# CODEC_2_OUTPUT_BUFFER.net
KiCad netlist of a schematic drawn in Altium Designer
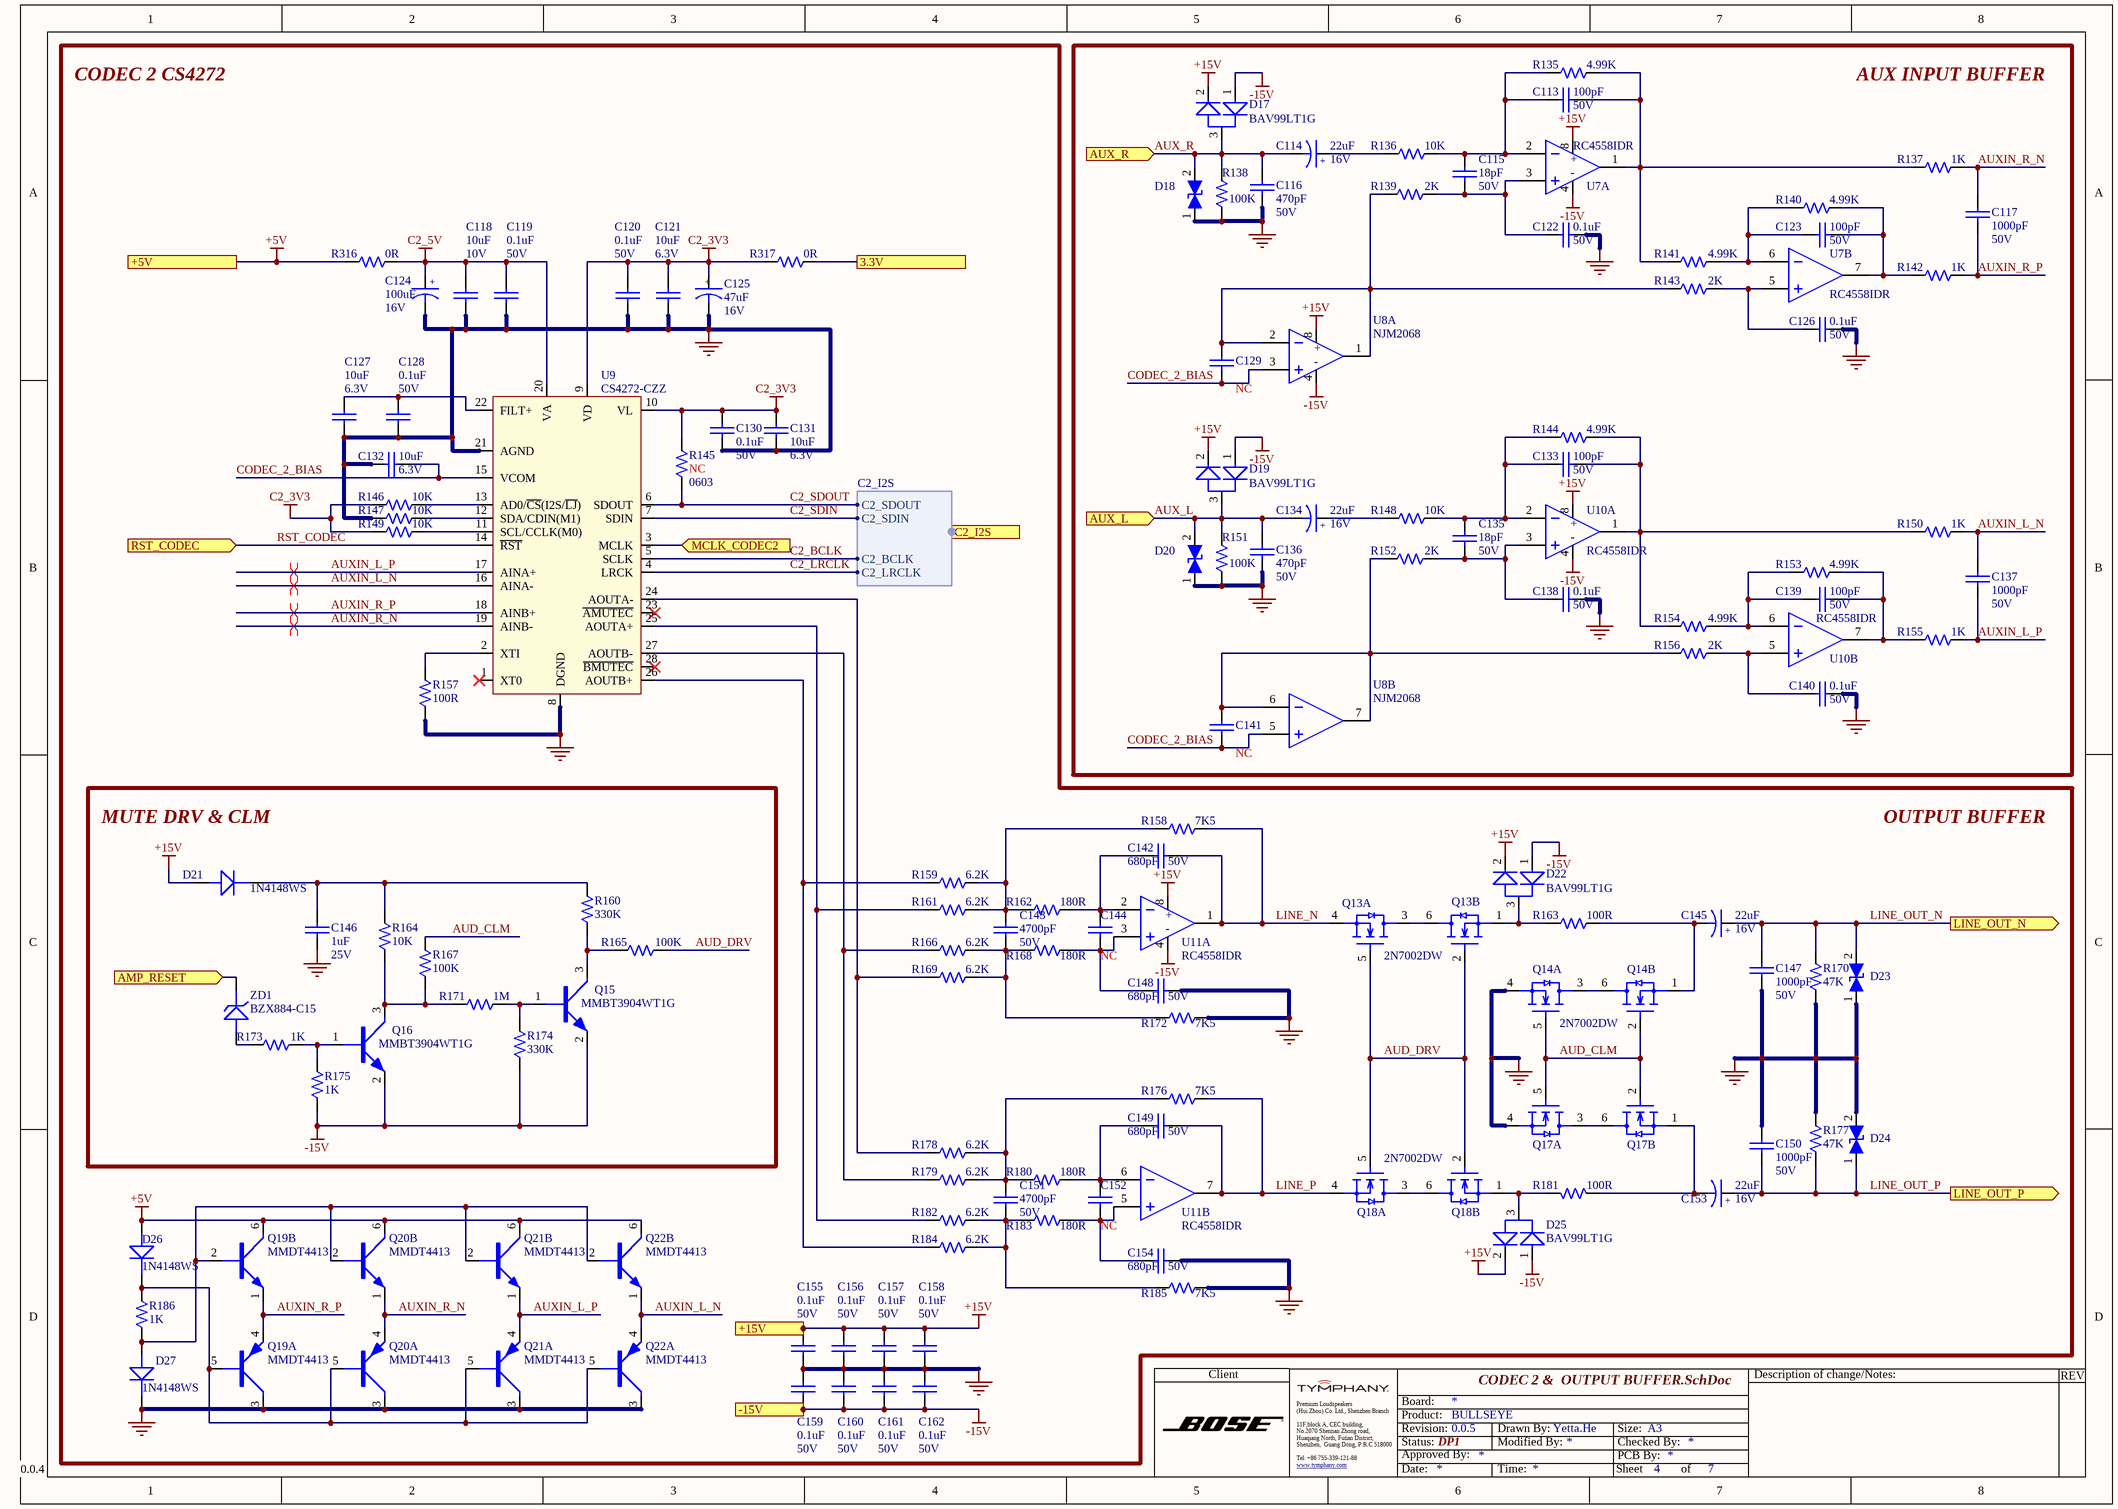
[diagram p0: CODEC 2 &  OUTPUT BUFFER.SchDoc]

(export (version "E")
  (design (tool "Eeschema 10.0.6"))
  (components
    (comp (ref "C113")
      (value "100pF")
      (footprint "CAPC0603-RW")
      (description "CAP NPO 100PF 50V +-2% 0603 WALSIN L")
      (fields
        (field (name "MFG") "WALSIN")
        (field (name "TOLERANCE") "2%")
        (field (name "VOLTAGE") "50V")
        (field (name "CREATE_NAME") "Nathan")
      )
      (libsource (lib "P-Capacitors") (part "CAP0603 100pF 50V 2%_NPO_WALSIN"))
    )
    (comp (ref "C114")
      (value "22uF")
      (footprint "CASE - B")
      (description "E 22UF 16V +-20% 4.3X4. VEJ220M1C K")
      (fields
        (field (name "MFG") "LELON")
        (field (name "MFG PART") "VEJ220M1CTR-0405")
        (field (name "VOLTAGE") "16V")
        (field (name "CREATE_NAME") "Nathan")
      )
      (libsource (lib "P-Capacitors") (part "CAP E 22uF 16V 20% SMD_VEJ220M1CTR-0405"))
    )
    (comp (ref "C115")
      (value "18pF")
      (footprint "P-Capacitors:CAPC0603-RW")
      (description "CHIP CAP 18pF 50V 5% 0603 TYPE NPO")
      (fields
        (field (name "TOLERANCE") "5%")
        (field (name "VOLTAGE") "50V")
        (field (name "Comment") "PXL410370-1800")
      )
      (libsource (lib "P-Capacitors") (part "CAP0603 18pF 50V 5% - PXL410370-1800"))
    )
    (comp (ref "C116")
      (value "470pF")
      (footprint "CAPC0603-RW")
      (description "CAP NPO 470PF 50V +-2% 0603 WALSIN L")
      (fields
        (field (name "MFG") "WALSIN")
        (field (name "TOLERANCE") "2%")
        (field (name "VOLTAGE") "50V")
        (field (name "CREATE_NAME") "Nathan")
      )
      (libsource (lib "P-Capacitors") (part "CAP0603 470pF 50V 2%_NPO_WALSIN"))
    )
    (comp (ref "C117")
      (value "1000pF")
      (footprint "CAPC0603-RW")
      (description "CAP NPO 1000P 50V +-2% 0603 WALSIN L")
      (fields
        (field (name "MFG") "WALSIN")
        (field (name "TOLERANCE") "2%")
        (field (name "VOLTAGE") "50V")
        (field (name "CREATE_NAME") "Nathan")
      )
      (libsource (lib "P-Capacitors") (part "CAP0603 1000pF 50V 2%_NPO_WALSIN"))
    )
    (comp (ref "C118")
      (value "10uF")
      (footprint "CAPC0603-RW")
      (description "CAP 10UF 10V +-20% 0603X5R SAMSUNG L")
      (fields
        (field (name "MFG") "SAMSUNG")
        (field (name "TOLERANCE") "20%,")
        (field (name "VOLTAGE") "10V")
        (field (name "CREATE_NAME") "Nathan")
      )
      (libsource (lib "P-Capacitors") (part "CAP0603 10uF 10V 20%_X5R_SAMSUNG"))
    )
    (comp (ref "C119")
      (value "0.1uF")
      (footprint "CAPC0402-RW")
      (description "CAP X7R .10UF 50V +-10% 0402 WALSIN L")
      (fields
        (field (name "TOLERANCE") "10%")
        (field (name "VOLTAGE") "50V")
        (field (name "Comment") "PWL456470-1040")
        (field (name "CREATE_NAME") "TOM@Deftronics")
      )
      (libsource (lib "P-Capacitors") (part "CAP0402 0.1uF 50V 10%"))
    )
    (comp (ref "C120")
      (value "0.1uF")
      (footprint "CAPC0402-RW")
      (description "CAP X7R .10UF 50V +-10% 0402 WALSIN L")
      (fields
        (field (name "TOLERANCE") "10%")
        (field (name "VOLTAGE") "50V")
        (field (name "Comment") "PWL456470-1040")
        (field (name "CREATE_NAME") "TOM@Deftronics")
      )
      (libsource (lib "P-Capacitors") (part "CAP0402 0.1uF 50V 10%"))
    )
    (comp (ref "C121")
      (value "10uF")
      (footprint "CAPC0603-RW")
      (description "CAP X5R 10UF 6.3V +-10% 0603 SAMSUN L")
      (fields
        (field (name "MFG") "SAMSUNG")
        (field (name "MFG PART") "CL10A106KQ8NNNC")
        (field (name "VOLTAGE") "6.3V")
        (field (name "CREATE_NAME") "Nathan")
      )
      (libsource (lib "P-Capacitors") (part "CAP0603 10uF 6.3V 10%_X5R_SAMSUNG"))
    )
    (comp (ref "C122")
      (value "0.1uF")
      (footprint "CAPC0603-RW")
      (description "GP CHIP CAP 0.1uF 50V 10% 0603 TYPE X7R")
      (fields
        (field (name "TOLERANCE") "10%")
        (field (name "VOLTAGE") "50V")
        (field (name "Comment") "PXL456470-1040")
      )
      (libsource (lib "P-Capacitors") (part "CAP0603 0.1uF 50V 10% - PXL456470-1040"))
    )
    (comp (ref "C123")
      (value "100pF")
      (footprint "CAPC0603-RW")
      (description "CAP NPO 100PF 50V +-2% 0603 WALSIN L")
      (fields
        (field (name "MFG") "WALSIN")
        (field (name "TOLERANCE") "2%")
        (field (name "VOLTAGE") "50V")
        (field (name "CREATE_NAME") "Nathan")
      )
      (libsource (lib "P-Capacitors") (part "CAP0603 100pF 50V 2%_NPO_WALSIN"))
    )
    (comp (ref "C124")
      (value "100uF")
      (footprint "CASE - D")
      (description "E 100UF 16V +-20% 6.3*5. VZH101M1C L")
      (fields
        (field (name "MFG") "LELON")
        (field (name "MFG PART") "VZH101M1CTR-0605")
        (field (name "VOLTAGE") "16V")
        (field (name "CREATE_NAME") "Nathan")
      )
      (libsource (lib "P-Capacitors") (part "CAP E 100uF 16V 20% SMD-VZH101M1CTR-0605"))
    )
    (comp (ref "C125")
      (value "47uF")
      (footprint "CASE - C5.7")
      (description "E 47UF 16V +-20% 5X6 VEJ470M1C K")
      (fields
        (field (name "MFG") "LELON")
        (field (name "MFG PART") "VEJ470M1CTR-0506")
        (field (name "VOLTAGE") "16V")
        (field (name "CREATE_NAME") "Nathan")
      )
      (libsource (lib "P-Capacitors") (part "CAP E 47uF 16V 20% SMD_VEJ470M1CTR-0506"))
    )
    (comp (ref "C126")
      (value "0.1uF")
      (footprint "CAPC0603-RW")
      (description "GP CHIP CAP 0.1uF 50V 10% 0603 TYPE X7R")
      (fields
        (field (name "TOLERANCE") "10%")
        (field (name "VOLTAGE") "50V")
        (field (name "Comment") "PXL456470-1040")
      )
      (libsource (lib "P-Capacitors") (part "CAP0603 0.1uF 50V 10% - PXL456470-1040"))
    )
    (comp (ref "C127")
      (value "10uF")
      (footprint "CAPC0603-RW")
      (description "CAP X5R 10UF 6.3V +-10% 0603 SAMSUN L")
      (fields
        (field (name "MFG") "SAMSUNG")
        (field (name "MFG PART") "CL10A106KQ8NNNC")
        (field (name "VOLTAGE") "6.3V")
        (field (name "CREATE_NAME") "Nathan")
      )
      (libsource (lib "P-Capacitors") (part "CAP0603 10uF 6.3V 10%_X5R_SAMSUNG"))
    )
    (comp (ref "C128")
      (value "0.1uF")
      (footprint "CAPC0402-RW")
      (description "CAP X7R .10UF 50V +-10% 0402 WALSIN L")
      (fields
        (field (name "TOLERANCE") "10%")
        (field (name "VOLTAGE") "50V")
        (field (name "Comment") "PWL456470-1040")
        (field (name "CREATE_NAME") "TOM@Deftronics")
      )
      (libsource (lib "P-Capacitors") (part "CAP0402 0.1uF 50V 10%"))
    )
    (comp (ref "C129")
      (value "NC")
      (footprint "CAPC0603-RW")
      (fields (field (name "Comment") "CAP0603 NC") (field (name "CREATE_NAME") "Tom"))
      (libsource (lib "Temporary") (part "CAP0603 NC"))
    )
    (comp (ref "C130")
      (value "0.1uF")
      (footprint "CAPC0402-RW")
      (description "CAP X7R .10UF 50V +-10% 0402 WALSIN L")
      (fields
        (field (name "TOLERANCE") "10%")
        (field (name "VOLTAGE") "50V")
        (field (name "Comment") "PWL456470-1040")
        (field (name "CREATE_NAME") "TOM@Deftronics")
      )
      (libsource (lib "P-Capacitors") (part "CAP0402 0.1uF 50V 10%"))
    )
    (comp (ref "C131")
      (value "10uF")
      (footprint "CAPC0603-RW")
      (description "CAP X5R 10UF 6.3V +-10% 0603 SAMSUN L")
      (fields
        (field (name "MFG") "SAMSUNG")
        (field (name "MFG PART") "CL10A106KQ8NNNC")
        (field (name "VOLTAGE") "6.3V")
        (field (name "CREATE_NAME") "Nathan")
      )
      (libsource (lib "P-Capacitors") (part "CAP0603 10uF 6.3V 10%_X5R_SAMSUNG"))
    )
    (comp (ref "C132")
      (value "10uF")
      (footprint "CAPC0603-RW")
      (description "CAP X5R 10UF 6.3V +-10% 0603 SAMSUN L")
      (fields
        (field (name "MFG") "SAMSUNG")
        (field (name "MFG PART") "CL10A106KQ8NNNC")
        (field (name "VOLTAGE") "6.3V")
        (field (name "CREATE_NAME") "Nathan")
      )
      (libsource (lib "P-Capacitors") (part "CAP0603 10uF 6.3V 10%_X5R_SAMSUNG"))
    )
    (comp (ref "C133")
      (value "100pF")
      (footprint "CAPC0603-RW")
      (description "CAP NPO 100PF 50V +-2% 0603 WALSIN L")
      (fields
        (field (name "MFG") "WALSIN")
        (field (name "TOLERANCE") "2%")
        (field (name "VOLTAGE") "50V")
        (field (name "CREATE_NAME") "Nathan")
      )
      (libsource (lib "P-Capacitors") (part "CAP0603 100pF 50V 2%_NPO_WALSIN"))
    )
    (comp (ref "C134")
      (value "22uF")
      (footprint "CASE - B")
      (description "E 22UF 16V +-20% 4.3X4. VEJ220M1C K")
      (fields
        (field (name "MFG") "LELON")
        (field (name "MFG PART") "VEJ220M1CTR-0405")
        (field (name "VOLTAGE") "16V")
        (field (name "CREATE_NAME") "Nathan")
      )
      (libsource (lib "P-Capacitors") (part "CAP E 22uF 16V 20% SMD_VEJ220M1CTR-0405"))
    )
    (comp (ref "C135")
      (value "18pF")
      (footprint "P-Capacitors:CAPC0603-RW")
      (description "CHIP CAP 18pF 50V 5% 0603 TYPE NPO")
      (fields
        (field (name "TOLERANCE") "5%")
        (field (name "VOLTAGE") "50V")
        (field (name "Comment") "PXL410370-1800")
      )
      (libsource (lib "P-Capacitors") (part "CAP0603 18pF 50V 5% - PXL410370-1800"))
    )
    (comp (ref "C136")
      (value "470pF")
      (footprint "CAPC0603-RW")
      (description "CAP NPO 470PF 50V +-2% 0603 WALSIN L")
      (fields
        (field (name "MFG") "WALSIN")
        (field (name "TOLERANCE") "2%")
        (field (name "VOLTAGE") "50V")
        (field (name "CREATE_NAME") "Nathan")
      )
      (libsource (lib "P-Capacitors") (part "CAP0603 470pF 50V 2%_NPO_WALSIN"))
    )
    (comp (ref "C137")
      (value "1000pF")
      (footprint "CAPC0603-RW")
      (description "CAP NPO 1000P 50V +-2% 0603 WALSIN L")
      (fields
        (field (name "MFG") "WALSIN")
        (field (name "TOLERANCE") "2%")
        (field (name "VOLTAGE") "50V")
        (field (name "CREATE_NAME") "Nathan")
      )
      (libsource (lib "P-Capacitors") (part "CAP0603 1000pF 50V 2%_NPO_WALSIN"))
    )
    (comp (ref "C138")
      (value "0.1uF")
      (footprint "CAPC0603-RW")
      (description "GP CHIP CAP 0.1uF 50V 10% 0603 TYPE X7R")
      (fields
        (field (name "TOLERANCE") "10%")
        (field (name "VOLTAGE") "50V")
        (field (name "Comment") "PXL456470-1040")
      )
      (libsource (lib "P-Capacitors") (part "CAP0603 0.1uF 50V 10% - PXL456470-1040"))
    )
    (comp (ref "C139")
      (value "100pF")
      (footprint "CAPC0603-RW")
      (description "CAP NPO 100PF 50V +-2% 0603 WALSIN L")
      (fields
        (field (name "MFG") "WALSIN")
        (field (name "TOLERANCE") "2%")
        (field (name "VOLTAGE") "50V")
        (field (name "CREATE_NAME") "Nathan")
      )
      (libsource (lib "P-Capacitors") (part "CAP0603 100pF 50V 2%_NPO_WALSIN"))
    )
    (comp (ref "C140")
      (value "0.1uF")
      (footprint "CAPC0603-RW")
      (description "GP CHIP CAP 0.1uF 50V 10% 0603 TYPE X7R")
      (fields
        (field (name "TOLERANCE") "10%")
        (field (name "VOLTAGE") "50V")
        (field (name "Comment") "PXL456470-1040")
      )
      (libsource (lib "P-Capacitors") (part "CAP0603 0.1uF 50V 10% - PXL456470-1040"))
    )
    (comp (ref "C141")
      (value "NC")
      (footprint "CAPC0603-RW")
      (fields (field (name "Comment") "CAP0603 NC") (field (name "CREATE_NAME") "Tom"))
      (libsource (lib "Temporary") (part "CAP0603 NC"))
    )
    (comp (ref "C142")
      (value "680pF")
      (footprint "CAPC0603-RW")
      (description "GP CHIP CAP 680pF 50V 5% 0603 NPO")
      (fields
        (field (name "TOLERANCE") "5%")
        (field (name "VOLTAGE") "50V")
        (field (name "Comment") "PXL410372-6810")
      )
      (libsource (lib "P-Capacitors") (part "CAP0603 680pF 50V 5% - PXL410372-6810"))
    )
    (comp (ref "C143")
      (value "4700pF")
      (footprint "CAPC0603-RW")
      (description "CAP X7R 4700P 50V +-10% 0603 WALSIN L")
      (fields
        (field (name "MFG") "WALSIN")
        (field (name "TOLERANCE") "10%")
        (field (name "VOLTAGE") "50V")
        (field (name "CREATE_NAME") "Nathan")
      )
      (libsource (lib "P-Capacitors") (part "CAP0603 4700pF 50V 10%_X7R_WALSIN"))
    )
    (comp (ref "C144")
      (value "NC")
      (footprint "CAPC0603-RW")
      (fields (field (name "Comment") "CAP0603 NC") (field (name "CREATE_NAME") "Tom"))
      (libsource (lib "Temporary") (part "CAP0603 NC"))
    )
    (comp (ref "C145")
      (value "22uF")
      (footprint "CASE - B")
      (description "E 22UF 16V +-20% 4.3X4. VEJ220M1C K")
      (fields
        (field (name "MFG") "LELON")
        (field (name "MFG PART") "VEJ220M1CTR-0405")
        (field (name "VOLTAGE") "16V")
        (field (name "CREATE_NAME") "Nathan")
      )
      (libsource (lib "P-Capacitors") (part "CAP E 22uF 16V 20% SMD_VEJ220M1CTR-0405"))
    )
    (comp (ref "C146")
      (value "1uF")
      (footprint "CAPC0603-RW")
      (description "CHIP CAP 1uF 25V 10% 0603 TYPE X7R")
      (fields
        (field (name "TOLERANCE") "10%")
        (field (name "VOLTAGE") "25V")
        (field (name "Comment") "PXL456450-1050")
      )
      (libsource (lib "P-Capacitors") (part "CAP0603 1uF 25V 10% - PXL456450-1050"))
    )
    (comp (ref "C147")
      (value "1000pF")
      (footprint "CAPC0603-RW")
      (description "CAP NPO 1000P 50V +-2% 0603 WALSIN L")
      (fields
        (field (name "MFG") "WALSIN")
        (field (name "TOLERANCE") "2%")
        (field (name "VOLTAGE") "50V")
        (field (name "CREATE_NAME") "Nathan")
      )
      (libsource (lib "P-Capacitors") (part "CAP0603 1000pF 50V 2%_NPO_WALSIN"))
    )
    (comp (ref "C148")
      (value "680pF")
      (footprint "CAPC0603-RW")
      (description "GP CHIP CAP 680pF 50V 5% 0603 NPO")
      (fields
        (field (name "TOLERANCE") "5%")
        (field (name "VOLTAGE") "50V")
        (field (name "Comment") "PXL410372-6810")
      )
      (libsource (lib "P-Capacitors") (part "CAP0603 680pF 50V 5% - PXL410372-6810"))
    )
    (comp (ref "C149")
      (value "680pF")
      (footprint "CAPC0603-RW")
      (description "GP CHIP CAP 680pF 50V 5% 0603 NPO")
      (fields
        (field (name "TOLERANCE") "5%")
        (field (name "VOLTAGE") "50V")
        (field (name "Comment") "PXL410372-6810")
      )
      (libsource (lib "P-Capacitors") (part "CAP0603 680pF 50V 5% - PXL410372-6810"))
    )
    (comp (ref "C150")
      (value "1000pF")
      (footprint "CAPC0603-RW")
      (description "CAP NPO 1000P 50V +-2% 0603 WALSIN L")
      (fields
        (field (name "MFG") "WALSIN")
        (field (name "TOLERANCE") "2%")
        (field (name "VOLTAGE") "50V")
        (field (name "CREATE_NAME") "Nathan")
      )
      (libsource (lib "P-Capacitors") (part "CAP0603 1000pF 50V 2%_NPO_WALSIN"))
    )
    (comp (ref "C151")
      (value "4700pF")
      (footprint "CAPC0603-RW")
      (description "CAP X7R 4700P 50V +-10% 0603 WALSIN L")
      (fields
        (field (name "MFG") "WALSIN")
        (field (name "TOLERANCE") "10%")
        (field (name "VOLTAGE") "50V")
        (field (name "CREATE_NAME") "Nathan")
      )
      (libsource (lib "P-Capacitors") (part "CAP0603 4700pF 50V 10%_X7R_WALSIN"))
    )
    (comp (ref "C152")
      (value "NC")
      (footprint "CAPC0603-RW")
      (fields (field (name "Comment") "CAP0603 NC") (field (name "CREATE_NAME") "Tom"))
      (libsource (lib "Temporary") (part "CAP0603 NC"))
    )
    (comp (ref "C153")
      (value "22uF")
      (footprint "CASE - B")
      (description "E 22UF 16V +-20% 4.3X4. VEJ220M1C K")
      (fields
        (field (name "MFG") "LELON")
        (field (name "MFG PART") "VEJ220M1CTR-0405")
        (field (name "VOLTAGE") "16V")
        (field (name "CREATE_NAME") "Nathan")
      )
      (libsource (lib "P-Capacitors") (part "CAP E 22uF 16V 20% SMD_VEJ220M1CTR-0405"))
    )
    (comp (ref "C154")
      (value "680pF")
      (footprint "CAPC0603-RW")
      (description "GP CHIP CAP 680pF 50V 5% 0603 NPO")
      (fields
        (field (name "TOLERANCE") "5%")
        (field (name "VOLTAGE") "50V")
        (field (name "Comment") "PXL410372-6810")
      )
      (libsource (lib "P-Capacitors") (part "CAP0603 680pF 50V 5% - PXL410372-6810"))
    )
    (comp (ref "C155")
      (value "0.1uF")
      (footprint "CAPC0402-RW")
      (description "CAP, CER, 0.1uF, 10%, 50V, X7R, 0402, RoHS")
      (fields
        (field (name "TOLERANCE") "10%")
        (field (name "VOLTAGE") "50V")
        (field (name "Comment") "PWL456470-1040")
        (field (name "CREATE_NAME") "TOM@Deftronics")
      )
      (libsource (lib "P-Capacitors") (part "CAP0402 0.1uF 50V 10%"))
    )
    (comp (ref "C156")
      (value "0.1uF")
      (footprint "CAPC0402-RW")
      (description "CAP, CER, 0.1uF, 10%, 50V, X7R, 0402, RoHS")
      (fields
        (field (name "TOLERANCE") "10%")
        (field (name "VOLTAGE") "50V")
        (field (name "Comment") "PWL456470-1040")
        (field (name "CREATE_NAME") "TOM@Deftronics")
      )
      (libsource (lib "P-Capacitors") (part "CAP0402 0.1uF 50V 10%"))
    )
    (comp (ref "C157")
      (value "0.1uF")
      (footprint "CAPC0402-RW")
      (description "CAP, CER, 0.1uF, 10%, 50V, X7R, 0402, RoHS")
      (fields
        (field (name "TOLERANCE") "10%")
        (field (name "VOLTAGE") "50V")
        (field (name "Comment") "PWL456470-1040")
        (field (name "CREATE_NAME") "TOM@Deftronics")
      )
      (libsource (lib "P-Capacitors") (part "CAP0402 0.1uF 50V 10%"))
    )
    (comp (ref "C158")
      (value "0.1uF")
      (footprint "CAPC0402-RW")
      (description "CAP, CER, 0.1uF, 10%, 50V, X7R, 0402, RoHS")
      (fields
        (field (name "TOLERANCE") "10%")
        (field (name "VOLTAGE") "50V")
        (field (name "Comment") "PWL456470-1040")
        (field (name "CREATE_NAME") "TOM@Deftronics")
      )
      (libsource (lib "P-Capacitors") (part "CAP0402 0.1uF 50V 10%"))
    )
    (comp (ref "C159")
      (value "0.1uF")
      (footprint "CAPC0402-RW")
      (description "CAP, CER, 0.1uF, 10%, 50V, X7R, 0402, RoHS")
      (fields
        (field (name "TOLERANCE") "10%")
        (field (name "VOLTAGE") "50V")
        (field (name "Comment") "PWL456470-1040")
        (field (name "CREATE_NAME") "TOM@Deftronics")
      )
      (libsource (lib "P-Capacitors") (part "CAP0402 0.1uF 50V 10%"))
    )
    (comp (ref "C160")
      (value "0.1uF")
      (footprint "CAPC0402-RW")
      (description "CAP, CER, 0.1uF, 10%, 50V, X7R, 0402, RoHS")
      (fields
        (field (name "TOLERANCE") "10%")
        (field (name "VOLTAGE") "50V")
        (field (name "Comment") "PWL456470-1040")
        (field (name "CREATE_NAME") "TOM@Deftronics")
      )
      (libsource (lib "P-Capacitors") (part "CAP0402 0.1uF 50V 10%"))
    )
    (comp (ref "C161")
      (value "0.1uF")
      (footprint "CAPC0402-RW")
      (description "CAP, CER, 0.1uF, 10%, 50V, X7R, 0402, RoHS")
      (fields
        (field (name "TOLERANCE") "10%")
        (field (name "VOLTAGE") "50V")
        (field (name "Comment") "PWL456470-1040")
        (field (name "CREATE_NAME") "TOM@Deftronics")
      )
      (libsource (lib "P-Capacitors") (part "CAP0402 0.1uF 50V 10%"))
    )
    (comp (ref "C162")
      (value "0.1uF")
      (footprint "CAPC0402-RW")
      (description "CAP, CER, 0.1uF, 10%, 50V, X7R, 0402, RoHS")
      (fields
        (field (name "TOLERANCE") "10%")
        (field (name "VOLTAGE") "50V")
        (field (name "Comment") "PWL456470-1040")
        (field (name "CREATE_NAME") "TOM@Deftronics")
      )
      (libsource (lib "P-Capacitors") (part "CAP0402 0.1uF 50V 10%"))
    )
    (comp (ref "D17")
      (value "RCD100099-0010")
      (footprint "SOT23-132-RW")
      (description "SWITC 70V 215MA BAV99LT1G ON SE G")
      (fields
        (field (name "MFG") "ON SEMI")
        (field (name "VOLTAGE") "100V")
        (field (name "MFG PART") "BAV99LT1G")
      )
      (libsource (lib "R-Semiconductors") (part "BAV99LT1G"))
    )
    (comp (ref "D18")
      (value "T710500020400")
      (footprint "VAR-0402")
      (description "VR AVRM1005C120MTAAB TDK K")
      (fields
        (field (name "MFG") "TDK")
        (field (name "MFG PART") "AVRM1005C120MTAAB")
        (field (name "CREAT NAME") "QCD")
      )
      (libsource (lib "R-Semiconductors") (part "AVRM1005C120MTAAB"))
    )
    (comp (ref "D19")
      (value "RCD100099-0010")
      (footprint "SOT23-132-RW")
      (description "SWITC 70V 215MA BAV99LT1G ON SE G")
      (fields
        (field (name "MFG") "ON SEMI")
        (field (name "VOLTAGE") "100V")
        (field (name "MFG PART") "BAV99LT1G")
      )
      (libsource (lib "R-Semiconductors") (part "BAV99LT1G"))
    )
    (comp (ref "D20")
      (value "T710500020400")
      (footprint "VAR-0402")
      (description "VR AVRM1005C120MTAAB TDK K")
      (fields
        (field (name "MFG") "TDK")
        (field (name "MFG PART") "AVRM1005C120MTAAB")
        (field (name "CREAT NAME") "QCD")
      )
      (libsource (lib "R-Semiconductors") (part "AVRM1005C120MTAAB"))
    )
    (comp (ref "D21")
      (value "RCD114148-0020")
      (footprint "SOD-323")
      (description "DIODE SW 1N4148 VF=0.7V SOD-323")
      (fields
        (field (name "MFG") "TW SEMICONDUCTOR")
        (field (name "VOLTAGE") "100V")
        (field (name "MFG PART") "1N4148WS")
      )
      (libsource (lib "R-Semiconductors") (part "1N4148WS"))
    )
    (comp (ref "D22")
      (value "RCD100099-0010")
      (footprint "SOT23-132-RW")
      (description "SWITC 70V 215MA BAV99LT1G ON SE G")
      (fields
        (field (name "MFG") "ON SEMI")
        (field (name "VOLTAGE") "100V")
        (field (name "MFG PART") "BAV99LT1G")
      )
      (libsource (lib "R-Semiconductors") (part "BAV99LT1G"))
    )
    (comp (ref "D23")
      (value "T710500020400")
      (footprint "VAR-0402")
      (description "VR AVRM1005C120MTAAB TDK K")
      (fields
        (field (name "MFG") "TDK")
        (field (name "MFG PART") "AVRM1005C120MTAAB")
        (field (name "CREAT NAME") "QCD")
      )
      (libsource (lib "R-Semiconductors") (part "AVRM1005C120MTAAB"))
    )
    (comp (ref "D24")
      (value "T710500020400")
      (footprint "VAR-0402")
      (description "VR AVRM1005C120MTAAB TDK K")
      (fields
        (field (name "MFG") "TDK")
        (field (name "MFG PART") "AVRM1005C120MTAAB")
        (field (name "CREAT NAME") "QCD")
      )
      (libsource (lib "R-Semiconductors") (part "AVRM1005C120MTAAB"))
    )
    (comp (ref "D25")
      (value "RCD100099-0010")
      (footprint "SOT23-132-RW")
      (description "SWITC 70V 215MA BAV99LT1G ON SE G")
      (fields
        (field (name "MFG") "ON SEMI")
        (field (name "VOLTAGE") "100V")
        (field (name "MFG PART") "BAV99LT1G")
      )
      (libsource (lib "R-Semiconductors") (part "BAV99LT1G"))
    )
    (comp (ref "D26")
      (value "RCD114148-0020")
      (footprint "SOD-323")
      (description "DIODE SW 1N4148 VF=0.7V SOD-323")
      (fields
        (field (name "MFG") "TW SEMICONDUCTOR")
        (field (name "VOLTAGE") "100V")
        (field (name "MFG PART") "1N4148WS")
      )
      (libsource (lib "R-Semiconductors") (part "1N4148WS"))
    )
    (comp (ref "D27")
      (value "RCD114148-0020")
      (footprint "SOD-323")
      (description "DIODE SW 1N4148 VF=0.7V SOD-323")
      (fields
        (field (name "MFG") "TW SEMICONDUCTOR")
        (field (name "VOLTAGE") "100V")
        (field (name "MFG PART") "1N4148WS")
      )
      (libsource (lib "R-Semiconductors") (part "1N4148WS"))
    )
    (comp (ref "Q13")
      (value "RCM027002-1001")
      (footprint "SOT-363")
      (description "SMD MOSFET N-CH SOT-363 2N7002DW      Fairchild")
      (fields
        (field (name "MFG") "Fairchild")
        (field (name "MFG PART") "2N7002DW")
        (field (name "CREATE_NAME") "Evan@Deftronics")
      )
      (libsource (lib "R-Semiconductors") (part "2N7002DW"))
    )
    (comp (ref "Q14")
      (value "RCM027002-1001")
      (footprint "SOT-363")
      (description "SMD MOSFET N-CH SOT-363 2N7002DW      Fairchild")
      (fields
        (field (name "MFG") "Fairchild")
        (field (name "MFG PART") "2N7002DW")
        (field (name "CREATE_NAME") "Evan@Deftronics")
      )
      (libsource (lib "R-Semiconductors") (part "2N7002DW"))
    )
    (comp (ref "Q15")
      (value "T581004222440")
      (footprint "SOT323(SC-70)-R")
      (description "NPN 40V MMBT3904WT1G SC70 ( ON K")
      (fields
        (field (name "MFG") "ON")
        (field (name "MFG PART") "MMBT3904WT1G")
        (field (name "CREATE_NAME") "Nathan")
      )
      (libsource (lib "R-Semiconductors") (part "MMBT3904WT1G"))
    )
    (comp (ref "Q16")
      (value "T581004222440")
      (footprint "SOT323(SC-70)-R")
      (description "NPN 40V MMBT3904WT1G SC70 ( ON K")
      (fields
        (field (name "MFG") "ON")
        (field (name "MFG PART") "MMBT3904WT1G")
        (field (name "CREATE_NAME") "Nathan")
      )
      (libsource (lib "R-Semiconductors") (part "MMBT3904WT1G"))
    )
    (comp (ref "Q17")
      (value "RCM027002-1001")
      (footprint "SOT-363")
      (description "SMD MOSFET N-CH SOT-363 2N7002DW      Fairchild")
      (fields (field (name "MFG") "Fairchild") (field (name "CREATE_NAME") "Evan@Deftronics"))
      (libsource (lib "") (part "2N7002DW_1"))
    )
    (comp (ref "Q18")
      (value "RCM027002-1001")
      (footprint "SOT-363")
      (description "SMD MOSFET N-CH SOT-363 2N7002DW      Fairchild")
      (fields
        (field (name "MFG") "Fairchild")
        (field (name "MFG PART") "2N7002DW")
        (field (name "CREATE_NAME") "Evan@Deftronics")
      )
      (libsource (lib "") (part "2N7002DW_1"))
    )
    (comp (ref "Q19")
      (value "RCC004413-0010")
      (footprint "SOT-363")
      (description "COMPOSOTE TRANSISTOR SOT-363 MMDT4413")
      (fields
        (field (name "MFG") "DIODES")
        (field (name "MFG_PART") "MMDT4413")
        (field (name "CREATE_NAME") "Nathan")
      )
      (libsource (lib "R-Semiconductors") (part "MMDT4413"))
    )
    (comp (ref "Q20")
      (value "RCC004413-0010")
      (footprint "SOT-363")
      (description "COMPOSOTE TRANSISTOR SOT-363 MMDT4413")
      (fields
        (field (name "MFG") "DIODES")
        (field (name "MFG_PART") "MMDT4413")
        (field (name "CREATE_NAME") "Nathan")
      )
      (libsource (lib "R-Semiconductors") (part "MMDT4413"))
    )
    (comp (ref "Q21")
      (value "RCC004413-0010")
      (footprint "SOT-363")
      (description "COMPOSOTE TRANSISTOR SOT-363 MMDT4413")
      (fields
        (field (name "MFG") "DIODES")
        (field (name "MFG_PART") "MMDT4413")
        (field (name "CREATE_NAME") "Nathan")
      )
      (libsource (lib "R-Semiconductors") (part "MMDT4413"))
    )
    (comp (ref "Q22")
      (value "RCC004413-0010")
      (footprint "SOT-363")
      (description "COMPOSOTE TRANSISTOR SOT-363 MMDT4413")
      (fields
        (field (name "MFG") "DIODES")
        (field (name "MFG_PART") "MMDT4413")
        (field (name "CREATE_NAME") "Nathan")
      )
      (libsource (lib "R-Semiconductors") (part "MMDT4413"))
    )
    (comp (ref "R135")
      (value "4.99K")
      (footprint "Q-Resistors:0603-RW")
      (description "GP CHIP RES. 4.99K OHM 1/10W 1% 0603")
      (fields (field (name "Comment") "QCF011030-4991"))
      (libsource (lib "Q-Resistors") (part "RES0603 1/10W 1% 4.99K OHM"))
    )
    (comp (ref "R136")
      (value "10K")
      (footprint "0603-RW")
      (description "GP CHIP RES. 10K OHM 1/10W 1% 0603")
      (fields (field (name "POWER") "1/10W") (field (name "Comment") "QCF011030-1002"))
      (libsource (lib "Q-Resistors") (part "RES0603 1/10W 1% 10K OHM"))
    )
    (comp (ref "R137")
      (value "1K")
      (footprint "0603-RW")
      (description "GP CHIP RES. 1K OHM 1/10W 1% 0603")
      (fields (field (name "POWER") "1/10W") (field (name "Comment") "QCF011030-1001"))
      (libsource (lib "Q-Resistors") (part "RES0603 1/10W 1% 1K OHM"))
    )
    (comp (ref "R138")
      (value "100K")
      (footprint "0603-RW")
      (description "GP CHIP RES. 100K OHM 1/10W 1% 0603")
      (fields (field (name "POWER") "1/10W") (field (name "Comment") "QCF011030-1003"))
      (libsource (lib "Q-Resistors") (part "RES0603 1/10W 1% 100K OHM"))
    )
    (comp (ref "R139")
      (value "2K")
      (footprint "0603-RW")
      (description "GP CHIP RES. 2K OHM 1/10W 1% 0603")
      (fields (field (name "Comment") "QCF011030-2001"))
      (libsource (lib "Q-Resistors") (part "RES0603 1/10W 1% 2K OHM"))
    )
    (comp (ref "R140")
      (value "4.99K")
      (footprint "Q-Resistors:0603-RW")
      (description "GP CHIP RES. 4.99K OHM 1/10W 1% 0603")
      (fields (field (name "Comment") "QCF011030-4991"))
      (libsource (lib "Q-Resistors") (part "RES0603 1/10W 1% 4.99K OHM"))
    )
    (comp (ref "R141")
      (value "4.99K")
      (footprint "Q-Resistors:0603-RW")
      (description "GP CHIP RES. 4.99K OHM 1/10W 1% 0603")
      (fields (field (name "Comment") "QCF011030-4991"))
      (libsource (lib "Q-Resistors") (part "RES0603 1/10W 1% 4.99K OHM"))
    )
    (comp (ref "R142")
      (value "1K")
      (footprint "0603-RW")
      (description "GP CHIP RES. 1K OHM 1/10W 1% 0603")
      (fields (field (name "POWER") "1/10W") (field (name "Comment") "QCF011030-1001"))
      (libsource (lib "Q-Resistors") (part "RES0603 1/10W 1% 1K OHM"))
    )
    (comp (ref "R143")
      (value "2K")
      (footprint "0603-RW")
      (description "GP CHIP RES. 2K OHM 1/10W 1% 0603")
      (fields (field (name "Comment") "QCF011030-2001"))
      (libsource (lib "Q-Resistors") (part "RES0603 1/10W 1% 2K OHM"))
    )
    (comp (ref "R144")
      (value "4.99K")
      (footprint "Q-Resistors:0603-RW")
      (description "GP CHIP RES. 4.99K OHM 1/10W 1% 0603")
      (fields (field (name "Comment") "QCF011030-4991"))
      (libsource (lib "Q-Resistors") (part "RES0603 1/10W 1% 4.99K OHM"))
    )
    (comp (ref "R145")
      (value "NC")
      (footprint "0603-RW")
      (fields
        (field (name "PACKAGE") "0603")
        (field (name "Comment") "RES0603 NC")
        (field (name "CREATE_NAME") "Tom")
      )
      (libsource (lib "Temporary") (part "RES0603 NC"))
    )
    (comp (ref "R146")
      (value "10K")
      (footprint "0402-RW")
      (description "CHIP RES 10K OHM 1/16W 1% 0402")
      (fields (field (name "POWER") "1/16W") (field (name "MFG") "WALSIN"))
      (libsource (lib "Q-Resistors") (part "RES0402 1/16W 1% 10K OHM"))
    )
    (comp (ref "R147")
      (value "10K")
      (footprint "0402-RW")
      (description "CHIP RES 10K OHM 1/16W 1% 0402")
      (fields (field (name "POWER") "1/16W") (field (name "MFG") "WALSIN"))
      (libsource (lib "Q-Resistors") (part "RES0402 1/16W 1% 10K OHM"))
    )
    (comp (ref "R148")
      (value "10K")
      (footprint "0603-RW")
      (description "GP CHIP RES. 10K OHM 1/10W 1% 0603")
      (fields (field (name "POWER") "1/10W") (field (name "Comment") "QCF011030-1002"))
      (libsource (lib "Q-Resistors") (part "RES0603 1/10W 1% 10K OHM"))
    )
    (comp (ref "R149")
      (value "10K")
      (footprint "0402-RW")
      (description "CHIP RES 10K OHM 1/16W 1% 0402")
      (fields (field (name "POWER") "1/16W") (field (name "MFG") "WALSIN"))
      (libsource (lib "Q-Resistors") (part "RES0402 1/16W 1% 10K OHM"))
    )
    (comp (ref "R150")
      (value "1K")
      (footprint "0603-RW")
      (description "GP CHIP RES. 1K OHM 1/10W 1% 0603")
      (fields (field (name "POWER") "1/10W") (field (name "Comment") "QCF011030-1001"))
      (libsource (lib "Q-Resistors") (part "RES0603 1/10W 1% 1K OHM"))
    )
    (comp (ref "R151")
      (value "100K")
      (footprint "0603-RW")
      (description "GP CHIP RES. 100K OHM 1/10W 1% 0603")
      (fields (field (name "POWER") "1/10W") (field (name "Comment") "QCF011030-1003"))
      (libsource (lib "Q-Resistors") (part "RES0603 1/10W 1% 100K OHM"))
    )
    (comp (ref "R152")
      (value "2K")
      (footprint "0603-RW")
      (description "GP CHIP RES. 2K OHM 1/10W 1% 0603")
      (fields (field (name "Comment") "QCF011030-2001"))
      (libsource (lib "Q-Resistors") (part "RES0603 1/10W 1% 2K OHM"))
    )
    (comp (ref "R153")
      (value "4.99K")
      (footprint "Q-Resistors:0603-RW")
      (description "GP CHIP RES. 4.99K OHM 1/10W 1% 0603")
      (fields (field (name "Comment") "QCF011030-4991"))
      (libsource (lib "Q-Resistors") (part "RES0603 1/10W 1% 4.99K OHM"))
    )
    (comp (ref "R154")
      (value "4.99K")
      (footprint "Q-Resistors:0603-RW")
      (description "GP CHIP RES. 4.99K OHM 1/10W 1% 0603")
      (fields (field (name "Comment") "QCF011030-4991"))
      (libsource (lib "Q-Resistors") (part "RES0603 1/10W 1% 4.99K OHM"))
    )
    (comp (ref "R155")
      (value "1K")
      (footprint "0603-RW")
      (description "GP CHIP RES. 1K OHM 1/10W 1% 0603")
      (fields (field (name "POWER") "1/10W") (field (name "Comment") "QCF011030-1001"))
      (libsource (lib "Q-Resistors") (part "RES0603 1/10W 1% 1K OHM"))
    )
    (comp (ref "R156")
      (value "2K")
      (footprint "0603-RW")
      (description "GP CHIP RES. 2K OHM 1/10W 1% 0603")
      (fields (field (name "Comment") "QCF011030-2001"))
      (libsource (lib "Q-Resistors") (part "RES0603 1/10W 1% 2K OHM"))
    )
    (comp (ref "R157")
      (value "100R")
      (footprint "0402-RW")
      (description "CHIP RES 100 OHM 1/16W 1% 0402")
      (fields (field (name "MFG") "WALSIN") (field (name "Comment") "QCF161240-1000"))
      (libsource (lib "Q-Resistors") (part "RES0402 1/16W 1% 100 OHM"))
    )
    (comp (ref "R158")
      (value "7K5")
      (footprint "0603-RW")
      (description "CHIP RES 7.5K OHM 1/10W 1% 0603")
      (fields
        (field (name "POWER") "1/10W")
        (field (name "Comment") "QCF011030-7501")
        (field (name "CREATE_NAME") "Nathan")
      )
      (libsource (lib "Q-Resistors") (part "RES0603 1/10W 1% 7.5K OHM"))
    )
    (comp (ref "R159")
      (value "6.2K")
      (footprint "0603-RW")
      (description "GP CHIP RES. 6.2K OHM 1/10W 1% 0603")
      (fields (field (name "POWER") "1/10W") (field (name "Comment") "QCF011030-6201"))
      (libsource (lib "Q-Resistors") (part "RES0603 1/10W 1% 6.2K OHM"))
    )
    (comp (ref "R160")
      (value "330K")
      (footprint "0402-RW")
      (description "CHIP 330K OHM  100PPM +-1% 0402 WALS")
      (fields
        (field (name "MFG") "WALSIN (華新)")
        (field (name "POWER") "1/16W")
        (field (name "CREATE_NAME") "Nathan")
      )
      (libsource (lib "Q-Resistors") (part "RES0402 1/16W 1% 330K OMH_WALSIN"))
    )
    (comp (ref "R161")
      (value "6.2K")
      (footprint "0603-RW")
      (description "GP CHIP RES. 6.2K OHM 1/10W 1% 0603")
      (fields (field (name "POWER") "1/10W") (field (name "Comment") "QCF011030-6201"))
      (libsource (lib "Q-Resistors") (part "RES0603 1/10W 1% 6.2K OHM"))
    )
    (comp (ref "R162")
      (value "180R")
      (footprint "0603-RW")
      (description "CHIP RES. 180 OHM 1/10W 1% 0603")
      (fields (field (name "POWER") "1/10W") (field (name "Comment") "QCF011030-1800"))
      (libsource (lib "Q-Resistors") (part "RES0603 1/10W 1% 180 OHM"))
    )
    (comp (ref "R163")
      (value "100R")
      (footprint "0603-RW")
      (description "CHIP 100 OHM 100PPM +-1% 0603 WALS L")
      (fields (field (name "POWER") "1/10W") (field (name "MFG") "WALSIN (華新)"))
      (libsource (lib "Q-Resistors") (part "RES0603 1/10W 1% 100 OHM"))
    )
    (comp (ref "R164")
      (value "10K")
      (footprint "0402-RW")
      (description "CHIP RES 10K OHM 1/16W 1% 0402")
      (fields (field (name "POWER") "1/16W") (field (name "MFG") "WALSIN"))
      (libsource (lib "Q-Resistors") (part "RES0402 1/16W 1% 10K OHM"))
    )
    (comp (ref "R165")
      (value "100K")
      (footprint "0603-RW")
      (description "GP CHIP RES. 100K OHM 1/10W 1% 0603")
      (fields (field (name "POWER") "1/10W") (field (name "Comment") "QCF011030-1003"))
      (libsource (lib "Q-Resistors") (part "RES0603 1/10W 1% 100K OHM"))
    )
    (comp (ref "R166")
      (value "6.2K")
      (footprint "0603-RW")
      (description "GP CHIP RES. 6.2K OHM 1/10W 1% 0603")
      (fields (field (name "POWER") "1/10W") (field (name "Comment") "QCF011030-6201"))
      (libsource (lib "Q-Resistors") (part "RES0603 1/10W 1% 6.2K OHM"))
    )
    (comp (ref "R167")
      (value "100K")
      (footprint "0603-RW")
      (description "GP CHIP RES. 100K OHM 1/10W 1% 0603")
      (fields (field (name "POWER") "1/10W") (field (name "Comment") "QCF011030-1003"))
      (libsource (lib "Q-Resistors") (part "RES0603 1/10W 1% 100K OHM"))
    )
    (comp (ref "R168")
      (value "180R")
      (footprint "0603-RW")
      (description "CHIP RES. 180 OHM 1/10W 1% 0603")
      (fields (field (name "POWER") "1/10W") (field (name "Comment") "QCF011030-1800"))
      (libsource (lib "Q-Resistors") (part "RES0603 1/10W 1% 180 OHM"))
    )
    (comp (ref "R169")
      (value "6.2K")
      (footprint "0603-RW")
      (description "GP CHIP RES. 6.2K OHM 1/10W 1% 0603")
      (fields (field (name "POWER") "1/10W") (field (name "Comment") "QCF011030-6201"))
      (libsource (lib "Q-Resistors") (part "RES0603 1/10W 1% 6.2K OHM"))
    )
    (comp (ref "R170")
      (value "47K")
      (footprint "0603-RW")
      (description "GP CHIP RES. 47K OHM 1/10W 1% 0603")
      (fields (field (name "Comment") "QCF011030-4702"))
      (libsource (lib "Q-Resistors") (part "RES0603 1/10W 1% 47K OHM"))
    )
    (comp (ref "R171")
      (value "1M")
      (footprint "0603-RW")
      (description "GP CHIP RES. 1M OHM 1/10W 1% 0603")
      (fields (field (name "POWER") "1/10W") (field (name "Comment") "QCF011030-1004"))
      (libsource (lib "Q-Resistors") (part "RES0603 1/10W 1% 1M OHM"))
    )
    (comp (ref "R172")
      (value "7K5")
      (footprint "0603-RW")
      (description "CHIP RES 7.5K OHM 1/10W 1% 0603")
      (fields
        (field (name "POWER") "1/10W")
        (field (name "Comment") "QCF011030-7501")
        (field (name "CREATE_NAME") "Nathan")
      )
      (libsource (lib "Q-Resistors") (part "RES0603 1/10W 1% 7.5K OHM"))
    )
    (comp (ref "R173")
      (value "1K")
      (footprint "0402-RW")
      (description "CHIP RES 1K OHM 1/16W 1% 0402")
      (fields (field (name "POWER") "1/16W") (field (name "MFG") "WALSIN"))
      (libsource (lib "Q-Resistors") (part "RES0402 1/16W 1% 1K OHM"))
    )
    (comp (ref "R174")
      (value "330K")
      (footprint "0402-RW")
      (description "CHIP 330K OHM  100PPM +-1% 0402 WALS")
      (fields
        (field (name "MFG") "WALSIN (華新)")
        (field (name "POWER") "1/16W")
        (field (name "CREATE_NAME") "Nathan")
      )
      (libsource (lib "Q-Resistors") (part "RES0402 1/16W 1% 330K OMH_WALSIN"))
    )
    (comp (ref "R175")
      (value "1K")
      (footprint "0402-RW")
      (description "CHIP RES 1K OHM 1/16W 1% 0402")
      (fields (field (name "POWER") "1/16W") (field (name "MFG") "WALSIN"))
      (libsource (lib "Q-Resistors") (part "RES0402 1/16W 1% 1K OHM"))
    )
    (comp (ref "R176")
      (value "7K5")
      (footprint "0603-RW")
      (description "CHIP RES 7.5K OHM 1/10W 1% 0603")
      (fields
        (field (name "POWER") "1/10W")
        (field (name "Comment") "QCF011030-7501")
        (field (name "CREATE_NAME") "Nathan")
      )
      (libsource (lib "Q-Resistors") (part "RES0603 1/10W 1% 7.5K OHM"))
    )
    (comp (ref "R177")
      (value "47K")
      (footprint "0603-RW")
      (description "GP CHIP RES. 47K OHM 1/10W 1% 0603")
      (fields (field (name "Comment") "QCF011030-4702"))
      (libsource (lib "Q-Resistors") (part "RES0603 1/10W 1% 47K OHM"))
    )
    (comp (ref "R178")
      (value "6.2K")
      (footprint "0603-RW")
      (description "GP CHIP RES. 6.2K OHM 1/10W 1% 0603")
      (fields (field (name "POWER") "1/10W") (field (name "Comment") "QCF011030-6201"))
      (libsource (lib "Q-Resistors") (part "RES0603 1/10W 1% 6.2K OHM"))
    )
    (comp (ref "R179")
      (value "6.2K")
      (footprint "0603-RW")
      (description "GP CHIP RES. 6.2K OHM 1/10W 1% 0603")
      (fields (field (name "POWER") "1/10W") (field (name "Comment") "QCF011030-6201"))
      (libsource (lib "Q-Resistors") (part "RES0603 1/10W 1% 6.2K OHM"))
    )
    (comp (ref "R180")
      (value "180R")
      (footprint "0603-RW")
      (description "CHIP RES. 180 OHM 1/10W 1% 0603")
      (fields (field (name "POWER") "1/10W") (field (name "Comment") "QCF011030-1800"))
      (libsource (lib "Q-Resistors") (part "RES0603 1/10W 1% 180 OHM"))
    )
    (comp (ref "R181")
      (value "100R")
      (footprint "0603-RW")
      (description "CHIP 100 OHM 100PPM +-1% 0603 WALS L")
      (fields (field (name "POWER") "1/10W") (field (name "MFG") "WALSIN (華新)"))
      (libsource (lib "Q-Resistors") (part "RES0603 1/10W 1% 100 OHM"))
    )
    (comp (ref "R182")
      (value "6.2K")
      (footprint "0603-RW")
      (description "GP CHIP RES. 6.2K OHM 1/10W 1% 0603")
      (fields (field (name "POWER") "1/10W") (field (name "Comment") "QCF011030-6201"))
      (libsource (lib "Q-Resistors") (part "RES0603 1/10W 1% 6.2K OHM"))
    )
    (comp (ref "R183")
      (value "180R")
      (footprint "0603-RW")
      (description "CHIP RES. 180 OHM 1/10W 1% 0603")
      (fields (field (name "POWER") "1/10W") (field (name "Comment") "QCF011030-1800"))
      (libsource (lib "Q-Resistors") (part "RES0603 1/10W 1% 180 OHM"))
    )
    (comp (ref "R184")
      (value "6.2K")
      (footprint "0603-RW")
      (description "GP CHIP RES. 6.2K OHM 1/10W 1% 0603")
      (fields (field (name "POWER") "1/10W") (field (name "Comment") "QCF011030-6201"))
      (libsource (lib "Q-Resistors") (part "RES0603 1/10W 1% 6.2K OHM"))
    )
    (comp (ref "R185")
      (value "7K5")
      (footprint "0603-RW")
      (description "CHIP RES 7.5K OHM 1/10W 1% 0603")
      (fields
        (field (name "POWER") "1/10W")
        (field (name "Comment") "QCF011030-7501")
        (field (name "CREATE_NAME") "Nathan")
      )
      (libsource (lib "Q-Resistors") (part "RES0603 1/10W 1% 7.5K OHM"))
    )
    (comp (ref "R186")
      (value "1K")
      (footprint "0603-RW")
      (description "GP CHIP RES. 1K OHM 1/10W 1% 0603")
      (fields (field (name "POWER") "1/10W") (field (name "Comment") "QCF011030-1001"))
      (libsource (lib "Q-Resistors") (part "RES0603 1/10W 1% 1K OHM"))
    )
    (comp (ref "R316")
      (value "0R")
      (footprint "0603-RW")
      (description "CHIP 0 OHM 0 OHM 0 OHM 0603 WALSIN L")
      (fields (field (name "POWER") "1/10W") (field (name "MFG PART") "WR06X000PTL"))
      (libsource (lib "Q-Resistors") (part "RES0603 1/10W 0 OHM_WALSIN"))
    )
    (comp (ref "R317")
      (value "0R")
      (footprint "0603-RW")
      (description "CHIP 0 OHM 0 OHM 0 OHM 0603 WALSIN L")
      (fields (field (name "POWER") "1/10W") (field (name "MFG PART") "WR06X000PTL"))
      (libsource (lib "Q-Resistors") (part "RES0603 1/10W 0 OHM_WALSIN"))
    )
    (comp (ref "U7")
      (value "T610500019101")
      (footprint "D(R-PDSO-G8)")
      (description "OP RC4558IDR SOP-8 TI G")
      (fields
        (field (name "MFG") "TI")
        (field (name "MFG PART") "RC4558IDR")
        (field (name "CREATE_NAME") "Nathan")
      )
      (libsource (lib "R-Semiconductors") (part "RC4558IDR"))
    )
    (comp (ref "U8")
      (value "RCI002068-0001")
      (footprint "DMP8")
      (description "IC OP AMP NJM2068 DUAL SO-8")
      (fields
        (field (name "MFG") "JRC")
        (field (name "MFG PART") "NJM2068")
        (field (name "CREATE_NAME") "GordonL@Deftronics")
      )
      (libsource (lib "R-Semiconductors") (part "NJM2068"))
    )
    (comp (ref "U9")
      (value "RCI004272-0001")
      (footprint "TSSOP28")
      (description "IC CODEC CS4272-CZZ TSSOP-28")
      (fields
        (field (name "MFG") "CIRRUS LOGIC")
        (field (name "MFG PART") "CS4272-CZZ")
        (field (name "CREATE_NAME") "GordonL@Deftronics")
      )
      (libsource (lib "R-Semiconductors") (part "CS4272-CZZ"))
    )
    (comp (ref "U10")
      (value "T610500019101")
      (footprint "D(R-PDSO-G8)")
      (description "OP RC4558IDR SOP-8 TI G")
      (fields
        (field (name "MFG") "TI")
        (field (name "MFG PART") "RC4558IDR")
        (field (name "CREATE_NAME") "Nathan")
      )
      (libsource (lib "R-Semiconductors") (part "RC4558IDR"))
    )
    (comp (ref "U11")
      (value "T610500019101")
      (footprint "D(R-PDSO-G8)")
      (description "OP RC4558IDR SOP-8 TI G")
      (fields
        (field (name "MFG") "TI")
        (field (name "MFG PART") "RC4558IDR")
        (field (name "CREATE_NAME") "Nathan")
      )
      (libsource (lib "R-Semiconductors") (part "RC4558IDR"))
    )
    (comp (ref "ZD1")
      (value "RCZ025015-0010")
      (footprint "SOD882")
      (description "CHIP ZENER 250mW SOD-882 BZX884-C15 15V")
      (fields
        (field (name "MFG") "NXP")
        (field (name "VOLTAGE") "15V")
        (field (name "MFG PART") "BZX884-C15")
        (field (name "CREATE_NAME") "XIN@Deftronics")
      )
      (libsource (lib "R-Semiconductors") (part "BZX884-C15"))
    )
  )
  (nets
    (net (code "2") (name "+5V") (class "Default")
      (node (ref "D26") (pin "1") (pinfunction "A_1") (pintype "passive"))
      (node (ref "Q19") (pin "6") (pinfunction "D_6") (pintype "passive"))
      (node (ref "Q20") (pin "6") (pinfunction "D_6") (pintype "passive"))
      (node (ref "Q21") (pin "6") (pinfunction "D_6") (pintype "passive"))
      (node (ref "Q22") (pin "6") (pinfunction "D_6") (pintype "passive"))
      (node (ref "R316") (pin "1") (pinfunction "1_1") (pintype "passive"))
    )
    (net (code "3") (name "+15V") (class "Default")
      (node (ref "C155") (pin "1") (pinfunction "1_1") (pintype "passive"))
      (node (ref "C156") (pin "1") (pinfunction "1_1") (pintype "passive"))
      (node (ref "C157") (pin "1") (pinfunction "1_1") (pintype "passive"))
      (node (ref "C158") (pin "1") (pinfunction "1_1") (pintype "passive"))
      (node (ref "D17") (pin "2") (pinfunction "K_2") (pintype "passive"))
      (node (ref "D19") (pin "2") (pinfunction "K_2") (pintype "passive"))
      (node (ref "D21") (pin "1") (pinfunction "A_1") (pintype "passive"))
      (node (ref "D22") (pin "2") (pinfunction "K_2") (pintype "passive"))
      (node (ref "D25") (pin "2") (pinfunction "K_2") (pintype "passive"))
      (node (ref "U10") (pin "8") (pinfunction "VCC+_8") (pintype "passive"))
      (node (ref "U11") (pin "8") (pinfunction "VCC+_8") (pintype "passive"))
      (node (ref "U7") (pin "8") (pinfunction "VCC+_8") (pintype "passive"))
      (node (ref "U8") (pin "8") (pinfunction "8_8") (pintype "passive"))
    )
    (net (code "4") (name "-15V") (class "Default")
      (node (ref "C159") (pin "2") (pinfunction "2_2") (pintype "passive"))
      (node (ref "C160") (pin "2") (pinfunction "2_2") (pintype "passive"))
      (node (ref "C161") (pin "2") (pinfunction "2_2") (pintype "passive"))
      (node (ref "C162") (pin "2") (pinfunction "2_2") (pintype "passive"))
      (node (ref "D17") (pin "1") (pinfunction "A_1") (pintype "passive"))
      (node (ref "D19") (pin "1") (pinfunction "A_1") (pintype "passive"))
      (node (ref "D22") (pin "1") (pinfunction "A_1") (pintype "passive"))
      (node (ref "D25") (pin "1") (pinfunction "A_1") (pintype "passive"))
      (node (ref "Q15") (pin "2") (pinfunction "E_2") (pintype "passive"))
      (node (ref "Q16") (pin "2") (pinfunction "E_2") (pintype "passive"))
      (node (ref "R174") (pin "1") (pinfunction "1_1") (pintype "passive"))
      (node (ref "R175") (pin "1") (pinfunction "1_1") (pintype "passive"))
      (node (ref "U10") (pin "4") (pinfunction "VCC-_4") (pintype "passive"))
      (node (ref "U11") (pin "4") (pinfunction "VCC-_4") (pintype "passive"))
      (node (ref "U7") (pin "4") (pinfunction "VCC-_4") (pintype "passive"))
      (node (ref "U8") (pin "4") (pinfunction "4_4") (pintype "passive"))
    )
    (net (code "5") (name "/3.3V") (class "Default")
      (node (ref "R317") (pin "2") (pinfunction "2_2") (pintype "passive"))
    )
    (net (code "6") (name "/AMP_RESET") (class "Default")
      (node (ref "ZD1") (pin "2") (pinfunction "K_2") (pintype "passive"))
    )
    (net (code "7") (name "/AUD_CLM") (class "Default")
      (node (ref "Q14") (pin "2") (pinfunction "G_2") (pintype "passive"))
      (node (ref "Q14") (pin "5") (pinfunction "G_5") (pintype "passive"))
      (node (ref "Q17") (pin "2") (pinfunction "G_2") (pintype "passive"))
      (node (ref "Q17") (pin "5") (pinfunction "G_5") (pintype "passive"))
      (node (ref "R167") (pin "2") (pinfunction "2_2") (pintype "passive"))
    )
    (net (code "8") (name "/AUD_DRV") (class "Default")
      (node (ref "Q13") (pin "2") (pinfunction "G_2") (pintype "passive"))
      (node (ref "Q13") (pin "5") (pinfunction "G_5") (pintype "passive"))
      (node (ref "Q18") (pin "2") (pinfunction "G_2") (pintype "passive"))
      (node (ref "Q18") (pin "5") (pinfunction "G_5") (pintype "passive"))
      (node (ref "R165") (pin "1") (pinfunction "1_1") (pintype "passive"))
    )
    (net (code "9") (name "/AUXIN_L_N") (class "Default")
      (node (ref "C137") (pin "1") (pinfunction "1_1") (pintype "passive"))
      (node (ref "Q22") (pin "1") (pinfunction "S_1") (pintype "passive"))
      (node (ref "Q22") (pin "4") (pinfunction "S_4") (pintype "passive"))
      (node (ref "R150") (pin "2") (pinfunction "2_2") (pintype "passive"))
      (node (ref "U9") (pin "16") (pinfunction "AINA-_16") (pintype "passive"))
    )
    (net (code "10") (name "/AUXIN_L_P") (class "Default")
      (node (ref "C137") (pin "2") (pinfunction "2_2") (pintype "passive"))
      (node (ref "Q21") (pin "1") (pinfunction "S_1") (pintype "passive"))
      (node (ref "Q21") (pin "4") (pinfunction "S_4") (pintype "passive"))
      (node (ref "R155") (pin "2") (pinfunction "2_2") (pintype "passive"))
      (node (ref "U9") (pin "17") (pinfunction "AINA+_17") (pintype "passive"))
    )
    (net (code "11") (name "/AUXIN_R_N") (class "Default")
      (node (ref "C117") (pin "1") (pinfunction "1_1") (pintype "passive"))
      (node (ref "Q20") (pin "1") (pinfunction "S_1") (pintype "passive"))
      (node (ref "Q20") (pin "4") (pinfunction "S_4") (pintype "passive"))
      (node (ref "R137") (pin "2") (pinfunction "2_2") (pintype "passive"))
      (node (ref "U9") (pin "19") (pinfunction "AINB-_19") (pintype "passive"))
    )
    (net (code "12") (name "/AUXIN_R_P") (class "Default")
      (node (ref "C117") (pin "2") (pinfunction "2_2") (pintype "passive"))
      (node (ref "Q19") (pin "1") (pinfunction "S_1") (pintype "passive"))
      (node (ref "Q19") (pin "4") (pinfunction "S_4") (pintype "passive"))
      (node (ref "R142") (pin "2") (pinfunction "2_2") (pintype "passive"))
      (node (ref "U9") (pin "18") (pinfunction "AINB+_18") (pintype "passive"))
    )
    (net (code "13") (name "/AUX_L") (class "Default")
      (node (ref "C134") (pin "2") (pinfunction "2_2") (pintype "passive"))
      (node (ref "C136") (pin "1") (pinfunction "1_1") (pintype "passive"))
      (node (ref "D19") (pin "3") (pinfunction "3_3") (pintype "passive"))
      (node (ref "D20") (pin "2") (pinfunction "2_2") (pintype "passive"))
      (node (ref "R151") (pin "2") (pinfunction "2_2") (pintype "passive"))
    )
    (net (code "14") (name "/AUX_R") (class "Default")
      (node (ref "C114") (pin "2") (pinfunction "2_2") (pintype "passive"))
      (node (ref "C116") (pin "1") (pinfunction "1_1") (pintype "passive"))
      (node (ref "D17") (pin "3") (pinfunction "3_3") (pintype "passive"))
      (node (ref "D18") (pin "2") (pinfunction "2_2") (pintype "passive"))
      (node (ref "R138") (pin "2") (pinfunction "2_2") (pintype "passive"))
    )
    (net (code "15") (name "/C2_BCLK") (class "Default")
      (node (ref "U9") (pin "5") (pinfunction "SCLK_5") (pintype "passive"))
    )
    (net (code "16") (name "/C2_LRCLK") (class "Default")
      (node (ref "U9") (pin "4") (pinfunction "LRCK_4") (pintype "passive"))
    )
    (net (code "17") (name "/C2_SDIN") (class "Default")
      (node (ref "U9") (pin "7") (pinfunction "SDIN_7") (pintype "passive"))
    )
    (net (code "18") (name "/C2_SDOUT") (class "Default")
      (node (ref "R145") (pin "1") (pinfunction "1_1") (pintype "passive"))
      (node (ref "U9") (pin "6") (pinfunction "SDOUT_6") (pintype "passive"))
    )
    (net (code "19") (name "/CODEC_2_BIAS") (class "Default")
      (node (ref "C129") (pin "2") (pinfunction "2_2") (pintype "passive"))
      (node (ref "C132") (pin "1") (pinfunction "1_1") (pintype "passive"))
      (node (ref "C141") (pin "2") (pinfunction "2_2") (pintype "passive"))
      (node (ref "U8") (pin "3") (pinfunction "IN+_3") (pintype "passive"))
      (node (ref "U8") (pin "5") (pinfunction "IN+_5") (pintype "passive"))
      (node (ref "U9") (pin "15") (pinfunction "VCOM_15") (pintype "passive"))
    )
    (net (code "20") (name "/LINE_N") (class "Default")
      (node (ref "C142") (pin "2") (pinfunction "2_2") (pintype "passive"))
      (node (ref "Q13") (pin "4") (pinfunction "S_4") (pintype "passive"))
      (node (ref "R158") (pin "2") (pinfunction "2_2") (pintype "passive"))
      (node (ref "U11") (pin "1") (pinfunction "1OUT_1") (pintype "passive"))
    )
    (net (code "21") (name "/LINE_OUT_N") (class "Default")
      (node (ref "C145") (pin "1") (pinfunction "1_1") (pintype "passive"))
      (node (ref "C147") (pin "2") (pinfunction "2_2") (pintype "passive"))
      (node (ref "D23") (pin "2") (pinfunction "2_2") (pintype "passive"))
      (node (ref "R170") (pin "2") (pinfunction "2_2") (pintype "passive"))
    )
    (net (code "22") (name "/LINE_OUT_P") (class "Default")
      (node (ref "C150") (pin "1") (pinfunction "1_1") (pintype "passive"))
      (node (ref "C153") (pin "1") (pinfunction "1_1") (pintype "passive"))
      (node (ref "D24") (pin "1") (pinfunction "1_1") (pintype "passive"))
      (node (ref "R177") (pin "1") (pinfunction "1_1") (pintype "passive"))
    )
    (net (code "23") (name "/LINE_P") (class "Default")
      (node (ref "C149") (pin "2") (pinfunction "2_2") (pintype "passive"))
      (node (ref "Q18") (pin "4") (pinfunction "S_4") (pintype "passive"))
      (node (ref "R176") (pin "2") (pinfunction "2_2") (pintype "passive"))
      (node (ref "U11") (pin "7") (pinfunction "2OUT_7") (pintype "passive"))
    )
    (net (code "24") (name "/MCLK_CODEC2") (class "Default")
      (node (ref "U9") (pin "3") (pinfunction "MCLK_3") (pintype "passive"))
    )
    (net (code "25") (name "/RST_CODEC") (class "Default")
      (node (ref "U9") (pin "14") (pinfunction "~{RST}_14") (pintype "passive"))
    )
    (net (code "27") (name "C2_3V3") (class "Default")
      (node (ref "C120") (pin "1") (pinfunction "1_1") (pintype "passive"))
      (node (ref "C121") (pin "1") (pinfunction "1_1") (pintype "passive"))
      (node (ref "C125") (pin "1") (pinfunction "1_1") (pintype "passive"))
      (node (ref "C130") (pin "2") (pinfunction "2_2") (pintype "passive"))
      (node (ref "C131") (pin "2") (pinfunction "2_2") (pintype "passive"))
      (node (ref "R145") (pin "2") (pinfunction "2_2") (pintype "passive"))
      (node (ref "R146") (pin "1") (pinfunction "1_1") (pintype "passive"))
      (node (ref "R149") (pin "1") (pinfunction "1_1") (pintype "passive"))
      (node (ref "R317") (pin "1") (pinfunction "1_1") (pintype "passive"))
      (node (ref "U9") (pin "10") (pinfunction "VL_10") (pintype "passive"))
      (node (ref "U9") (pin "9") (pinfunction "VD_9") (pintype "passive"))
    )
    (net (code "28") (name "C2_5V") (class "Default")
      (node (ref "C118") (pin "1") (pinfunction "1_1") (pintype "passive"))
      (node (ref "C119") (pin "1") (pinfunction "1_1") (pintype "passive"))
      (node (ref "C124") (pin "1") (pinfunction "1_1") (pintype "passive"))
      (node (ref "R316") (pin "2") (pinfunction "2_2") (pintype "passive"))
      (node (ref "U9") (pin "20") (pinfunction "VA_20") (pintype "passive"))
    )
    (net (code "29") (name "GND") (class "Default")
      (node (ref "C116") (pin "2") (pinfunction "2_2") (pintype "passive"))
      (node (ref "C118") (pin "2") (pinfunction "2_2") (pintype "passive"))
      (node (ref "C119") (pin "2") (pinfunction "2_2") (pintype "passive"))
      (node (ref "C120") (pin "2") (pinfunction "2_2") (pintype "passive"))
      (node (ref "C121") (pin "2") (pinfunction "2_2") (pintype "passive"))
      (node (ref "C122") (pin "2") (pinfunction "2_2") (pintype "passive"))
      (node (ref "C124") (pin "2") (pinfunction "2_2") (pintype "passive"))
      (node (ref "C125") (pin "2") (pinfunction "2_2") (pintype "passive"))
      (node (ref "C126") (pin "2") (pinfunction "2_2") (pintype "passive"))
      (node (ref "C127") (pin "1") (pinfunction "1_1") (pintype "passive"))
      (node (ref "C128") (pin "2") (pinfunction "2_2") (pintype "passive"))
      (node (ref "C130") (pin "1") (pinfunction "1_1") (pintype "passive"))
      (node (ref "C131") (pin "1") (pinfunction "1_1") (pintype "passive"))
      (node (ref "C132") (pin "2") (pinfunction "2_2") (pintype "passive"))
      (node (ref "C136") (pin "2") (pinfunction "2_2") (pintype "passive"))
      (node (ref "C138") (pin "2") (pinfunction "2_2") (pintype "passive"))
      (node (ref "C140") (pin "2") (pinfunction "2_2") (pintype "passive"))
      (node (ref "C146") (pin "2") (pinfunction "2_2") (pintype "passive"))
      (node (ref "C147") (pin "1") (pinfunction "1_1") (pintype "passive"))
      (node (ref "C148") (pin "2") (pinfunction "2_2") (pintype "passive"))
      (node (ref "C150") (pin "2") (pinfunction "2_2") (pintype "passive"))
      (node (ref "C154") (pin "2") (pinfunction "2_2") (pintype "passive"))
      (node (ref "C155") (pin "2") (pinfunction "2_2") (pintype "passive"))
      (node (ref "C156") (pin "2") (pinfunction "2_2") (pintype "passive"))
      (node (ref "C157") (pin "2") (pinfunction "2_2") (pintype "passive"))
      (node (ref "C158") (pin "2") (pinfunction "2_2") (pintype "passive"))
      (node (ref "C159") (pin "1") (pinfunction "1_1") (pintype "passive"))
      (node (ref "C160") (pin "1") (pinfunction "1_1") (pintype "passive"))
      (node (ref "C161") (pin "1") (pinfunction "1_1") (pintype "passive"))
      (node (ref "C162") (pin "1") (pinfunction "1_1") (pintype "passive"))
      (node (ref "D18") (pin "1") (pinfunction "1_1") (pintype "passive"))
      (node (ref "D20") (pin "1") (pinfunction "1_1") (pintype "passive"))
      (node (ref "D23") (pin "1") (pinfunction "1_1") (pintype "passive"))
      (node (ref "D24") (pin "2") (pinfunction "2_2") (pintype "passive"))
      (node (ref "D27") (pin "2") (pinfunction "K_2") (pintype "passive"))
      (node (ref "Q14") (pin "4") (pinfunction "S_4") (pintype "passive"))
      (node (ref "Q17") (pin "4") (pinfunction "S_4") (pintype "passive"))
      (node (ref "Q19") (pin "3") (pinfunction "D_3") (pintype "passive"))
      (node (ref "Q20") (pin "3") (pinfunction "D_3") (pintype "passive"))
      (node (ref "Q21") (pin "3") (pinfunction "D_3") (pintype "passive"))
      (node (ref "Q22") (pin "3") (pinfunction "D_3") (pintype "passive"))
      (node (ref "R138") (pin "1") (pinfunction "1_1") (pintype "passive"))
      (node (ref "R147") (pin "1") (pinfunction "1_1") (pintype "passive"))
      (node (ref "R151") (pin "1") (pinfunction "1_1") (pintype "passive"))
      (node (ref "R157") (pin "1") (pinfunction "1_1") (pintype "passive"))
      (node (ref "R170") (pin "1") (pinfunction "1_1") (pintype "passive"))
      (node (ref "R172") (pin "2") (pinfunction "2_2") (pintype "passive"))
      (node (ref "R177") (pin "2") (pinfunction "2_2") (pintype "passive"))
      (node (ref "R185") (pin "2") (pinfunction "2_2") (pintype "passive"))
      (node (ref "U9") (pin "21") (pinfunction "AGND_21") (pintype "passive"))
      (node (ref "U9") (pin "8") (pinfunction "DGND_8") (pintype "passive"))
    )
    (net (code "30") (name "Net-(C114-Pad1)") (class "Default")
      (node (ref "C114") (pin "1") (pinfunction "1_1") (pintype "passive"))
      (node (ref "R136") (pin "1") (pinfunction "1_1") (pintype "passive"))
    )
    (net (code "31") (name "Net-(C134-Pad1)") (class "Default")
      (node (ref "C134") (pin "1") (pinfunction "1_1") (pintype "passive"))
      (node (ref "R148") (pin "1") (pinfunction "1_1") (pintype "passive"))
    )
    (net (code "32") (name "Net-(C143-Pad1)") (class "Default")
      (node (ref "C143") (pin "1") (pinfunction "1_1") (pintype "passive"))
      (node (ref "R158") (pin "1") (pinfunction "1_1") (pintype "passive"))
      (node (ref "R159") (pin "2") (pinfunction "2_2") (pintype "passive"))
      (node (ref "R161") (pin "2") (pinfunction "2_2") (pintype "passive"))
      (node (ref "R162") (pin "1") (pinfunction "1_1") (pintype "passive"))
    )
    (net (code "33") (name "Net-(C143-Pad2)") (class "Default")
      (node (ref "C143") (pin "2") (pinfunction "2_2") (pintype "passive"))
      (node (ref "R166") (pin "2") (pinfunction "2_2") (pintype "passive"))
      (node (ref "R168") (pin "1") (pinfunction "1_1") (pintype "passive"))
      (node (ref "R169") (pin "2") (pinfunction "2_2") (pintype "passive"))
      (node (ref "R172") (pin "1") (pinfunction "1_1") (pintype "passive"))
    )
    (net (code "34") (name "Net-(C151-Pad1)") (class "Default")
      (node (ref "C151") (pin "1") (pinfunction "1_1") (pintype "passive"))
      (node (ref "R176") (pin "1") (pinfunction "1_1") (pintype "passive"))
      (node (ref "R178") (pin "2") (pinfunction "2_2") (pintype "passive"))
      (node (ref "R179") (pin "2") (pinfunction "2_2") (pintype "passive"))
      (node (ref "R180") (pin "1") (pinfunction "1_1") (pintype "passive"))
    )
    (net (code "35") (name "Net-(C151-Pad2)") (class "Default")
      (node (ref "C151") (pin "2") (pinfunction "2_2") (pintype "passive"))
      (node (ref "R182") (pin "2") (pinfunction "2_2") (pintype "passive"))
      (node (ref "R183") (pin "1") (pinfunction "1_1") (pintype "passive"))
      (node (ref "R184") (pin "2") (pinfunction "2_2") (pintype "passive"))
      (node (ref "R185") (pin "1") (pinfunction "1_1") (pintype "passive"))
    )
    (net (code "36") (name "Net-(D21-K)") (class "Default")
      (node (ref "C146") (pin "1") (pinfunction "1_1") (pintype "passive"))
      (node (ref "D21") (pin "2") (pinfunction "K_2") (pintype "passive"))
      (node (ref "R160") (pin "2") (pinfunction "2_2") (pintype "passive"))
      (node (ref "R164") (pin "2") (pinfunction "2_2") (pintype "passive"))
    )
    (net (code "37") (name "Net-(D26-K)") (class "Default")
      (node (ref "D26") (pin "2") (pinfunction "K_2") (pintype "passive"))
      (node (ref "Q19") (pin "5") (pinfunction "G_5") (pintype "passive"))
      (node (ref "Q20") (pin "5") (pinfunction "G_5") (pintype "passive"))
      (node (ref "Q21") (pin "5") (pinfunction "G_5") (pintype "passive"))
      (node (ref "Q22") (pin "5") (pinfunction "G_5") (pintype "passive"))
      (node (ref "R186") (pin "2") (pinfunction "2_2") (pintype "passive"))
    )
    (net (code "38") (name "Net-(D27-A)") (class "Default")
      (node (ref "D27") (pin "1") (pinfunction "A_1") (pintype "passive"))
      (node (ref "Q19") (pin "2") (pinfunction "G_2") (pintype "passive"))
      (node (ref "Q20") (pin "2") (pinfunction "G_2") (pintype "passive"))
      (node (ref "Q21") (pin "2") (pinfunction "G_2") (pintype "passive"))
      (node (ref "Q22") (pin "2") (pinfunction "G_2") (pintype "passive"))
      (node (ref "R186") (pin "1") (pinfunction "1_1") (pintype "passive"))
    )
    (net (code "39") (name "Net-(Q13A-D)") (class "Default")
      (node (ref "Q13") (pin "3") (pinfunction "D_3") (pintype "passive"))
      (node (ref "Q13") (pin "6") (pinfunction "D_6") (pintype "passive"))
    )
    (net (code "40") (name "Net-(Q13B-S)") (class "Default")
      (node (ref "D22") (pin "3") (pinfunction "3_3") (pintype "passive"))
      (node (ref "Q13") (pin "1") (pinfunction "S_1") (pintype "passive"))
      (node (ref "R163") (pin "1") (pinfunction "1_1") (pintype "passive"))
    )
    (net (code "41") (name "Net-(Q14A-D)") (class "Default")
      (node (ref "Q14") (pin "3") (pinfunction "D_3") (pintype "passive"))
      (node (ref "Q14") (pin "6") (pinfunction "D_6") (pintype "passive"))
    )
    (net (code "42") (name "Net-(Q14B-S)") (class "Default")
      (node (ref "C145") (pin "2") (pinfunction "2_2") (pintype "passive"))
      (node (ref "Q14") (pin "1") (pinfunction "S_1") (pintype "passive"))
      (node (ref "R163") (pin "2") (pinfunction "2_2") (pintype "passive"))
    )
    (net (code "43") (name "Net-(Q15-B)") (class "Default")
      (node (ref "Q15") (pin "1") (pinfunction "B_1") (pintype "passive"))
      (node (ref "R171") (pin "2") (pinfunction "2_2") (pintype "passive"))
      (node (ref "R174") (pin "2") (pinfunction "2_2") (pintype "passive"))
    )
    (net (code "44") (name "Net-(Q15-C)") (class "Default")
      (node (ref "Q15") (pin "3") (pinfunction "C_3") (pintype "passive"))
      (node (ref "R160") (pin "1") (pinfunction "1_1") (pintype "passive"))
      (node (ref "R165") (pin "2") (pinfunction "2_2") (pintype "passive"))
    )
    (net (code "45") (name "Net-(Q16-B)") (class "Default")
      (node (ref "Q16") (pin "1") (pinfunction "B_1") (pintype "passive"))
      (node (ref "R173") (pin "1") (pinfunction "1_1") (pintype "passive"))
      (node (ref "R175") (pin "2") (pinfunction "2_2") (pintype "passive"))
    )
    (net (code "46") (name "Net-(Q16-C)") (class "Default")
      (node (ref "Q16") (pin "3") (pinfunction "C_3") (pintype "passive"))
      (node (ref "R164") (pin "1") (pinfunction "1_1") (pintype "passive"))
      (node (ref "R167") (pin "1") (pinfunction "1_1") (pintype "passive"))
      (node (ref "R171") (pin "1") (pinfunction "1_1") (pintype "passive"))
    )
    (net (code "47") (name "Net-(Q17A-D)") (class "Default")
      (node (ref "Q17") (pin "3") (pinfunction "D_3") (pintype "passive"))
      (node (ref "Q17") (pin "6") (pinfunction "D_6") (pintype "passive"))
    )
    (net (code "48") (name "Net-(Q17B-S)") (class "Default")
      (node (ref "C153") (pin "2") (pinfunction "2_2") (pintype "passive"))
      (node (ref "Q17") (pin "1") (pinfunction "S_1") (pintype "passive"))
      (node (ref "R181") (pin "2") (pinfunction "2_2") (pintype "passive"))
    )
    (net (code "49") (name "Net-(Q18A-D)") (class "Default")
      (node (ref "Q18") (pin "3") (pinfunction "D_3") (pintype "passive"))
      (node (ref "Q18") (pin "6") (pinfunction "D_6") (pintype "passive"))
    )
    (net (code "50") (name "Net-(Q18B-S)") (class "Default")
      (node (ref "D25") (pin "3") (pinfunction "3_3") (pintype "passive"))
      (node (ref "Q18") (pin "1") (pinfunction "S_1") (pintype "passive"))
      (node (ref "R181") (pin "1") (pinfunction "1_1") (pintype "passive"))
    )
    (net (code "51") (name "Net-(U7A-1IN+)") (class "Default")
      (node (ref "C115") (pin "2") (pinfunction "2_2") (pintype "passive"))
      (node (ref "C122") (pin "1") (pinfunction "1_1") (pintype "passive"))
      (node (ref "R139") (pin "1") (pinfunction "1_1") (pintype "passive"))
      (node (ref "U7") (pin "3") (pinfunction "1IN+_3") (pintype "passive"))
    )
    (net (code "52") (name "Net-(U7A-1IN-)") (class "Default")
      (node (ref "C113") (pin "1") (pinfunction "1_1") (pintype "passive"))
      (node (ref "C115") (pin "1") (pinfunction "1_1") (pintype "passive"))
      (node (ref "R135") (pin "1") (pinfunction "1_1") (pintype "passive"))
      (node (ref "R136") (pin "2") (pinfunction "2_2") (pintype "passive"))
      (node (ref "U7") (pin "2") (pinfunction "1IN-_2") (pintype "passive"))
    )
    (net (code "53") (name "Net-(U7A-1OUT)") (class "Default")
      (node (ref "C113") (pin "2") (pinfunction "2_2") (pintype "passive"))
      (node (ref "R135") (pin "2") (pinfunction "2_2") (pintype "passive"))
      (node (ref "R137") (pin "1") (pinfunction "1_1") (pintype "passive"))
      (node (ref "R141") (pin "2") (pinfunction "2_2") (pintype "passive"))
      (node (ref "U7") (pin "1") (pinfunction "1OUT_1") (pintype "passive"))
    )
    (net (code "54") (name "Net-(U7B-2IN+)") (class "Default")
      (node (ref "C126") (pin "1") (pinfunction "1_1") (pintype "passive"))
      (node (ref "R143") (pin "1") (pinfunction "1_1") (pintype "passive"))
      (node (ref "U7") (pin "5") (pinfunction "2IN+_5") (pintype "passive"))
    )
    (net (code "55") (name "Net-(U7B-2IN-)") (class "Default")
      (node (ref "C123") (pin "1") (pinfunction "1_1") (pintype "passive"))
      (node (ref "R140") (pin "1") (pinfunction "1_1") (pintype "passive"))
      (node (ref "R141") (pin "1") (pinfunction "1_1") (pintype "passive"))
      (node (ref "U7") (pin "6") (pinfunction "2IN-_6") (pintype "passive"))
    )
    (net (code "56") (name "Net-(U7B-2OUT)") (class "Default")
      (node (ref "C123") (pin "2") (pinfunction "2_2") (pintype "passive"))
      (node (ref "R140") (pin "2") (pinfunction "2_2") (pintype "passive"))
      (node (ref "R142") (pin "1") (pinfunction "1_1") (pintype "passive"))
      (node (ref "U7") (pin "7") (pinfunction "2OUT_7") (pintype "passive"))
    )
    (net (code "57") (name "Net-(U8A-IN-)") (class "Default")
      (node (ref "C129") (pin "1") (pinfunction "1_1") (pintype "passive"))
      (node (ref "R139") (pin "2") (pinfunction "2_2") (pintype "passive"))
      (node (ref "R143") (pin "2") (pinfunction "2_2") (pintype "passive"))
      (node (ref "U8") (pin "1") (pinfunction "OUT_1") (pintype "passive"))
      (node (ref "U8") (pin "2") (pinfunction "IN-_2") (pintype "passive"))
    )
    (net (code "58") (name "Net-(U8B-IN-)") (class "Default")
      (node (ref "C141") (pin "1") (pinfunction "1_1") (pintype "passive"))
      (node (ref "R152") (pin "2") (pinfunction "2_2") (pintype "passive"))
      (node (ref "R156") (pin "2") (pinfunction "2_2") (pintype "passive"))
      (node (ref "U8") (pin "6") (pinfunction "IN-_6") (pintype "passive"))
      (node (ref "U8") (pin "7") (pinfunction "OUT_7") (pintype "passive"))
    )
    (net (code "59") (name "Net-(U9-AD0{slash}~{CS}(I2S{slash}~{LJ}))") (class "Default")
      (node (ref "R146") (pin "2") (pinfunction "2_2") (pintype "passive"))
      (node (ref "U9") (pin "13") (pinfunction "AD0/~{CS}(I2S/~{LJ})_13") (pintype "passive"))
    )
    (net (code "60") (name "Net-(U9-AOUTA+)") (class "Default")
      (node (ref "R161") (pin "1") (pinfunction "1_1") (pintype "passive"))
      (node (ref "R182") (pin "1") (pinfunction "1_1") (pintype "passive"))
      (node (ref "U9") (pin "25") (pinfunction "AOUTA+_25") (pintype "passive"))
    )
    (net (code "61") (name "Net-(U9-AOUTA-)") (class "Default")
      (node (ref "R169") (pin "1") (pinfunction "1_1") (pintype "passive"))
      (node (ref "R178") (pin "1") (pinfunction "1_1") (pintype "passive"))
      (node (ref "U9") (pin "24") (pinfunction "AOUTA-_24") (pintype "passive"))
    )
    (net (code "62") (name "Net-(U9-AOUTB+)") (class "Default")
      (node (ref "R159") (pin "1") (pinfunction "1_1") (pintype "passive"))
      (node (ref "R184") (pin "1") (pinfunction "1_1") (pintype "passive"))
      (node (ref "U9") (pin "26") (pinfunction "AOUTB+_26") (pintype "passive"))
    )
    (net (code "63") (name "Net-(U9-AOUTB-)") (class "Default")
      (node (ref "R166") (pin "1") (pinfunction "1_1") (pintype "passive"))
      (node (ref "R179") (pin "1") (pinfunction "1_1") (pintype "passive"))
      (node (ref "U9") (pin "27") (pinfunction "AOUTB-_27") (pintype "passive"))
    )
    (net (code "64") (name "Net-(U9-FILT+)") (class "Default")
      (node (ref "C127") (pin "2") (pinfunction "2_2") (pintype "passive"))
      (node (ref "C128") (pin "1") (pinfunction "1_1") (pintype "passive"))
      (node (ref "U9") (pin "22") (pinfunction "FILT+_22") (pintype "passive"))
    )
    (net (code "65") (name "Net-(U9-SCL{slash}CCLK(M0))") (class "Default")
      (node (ref "R149") (pin "2") (pinfunction "2_2") (pintype "passive"))
      (node (ref "U9") (pin "11") (pinfunction "SCL/CCLK(M0)_11") (pintype "passive"))
    )
    (net (code "66") (name "Net-(U9-SDA{slash}CDIN(M1))") (class "Default")
      (node (ref "R147") (pin "2") (pinfunction "2_2") (pintype "passive"))
      (node (ref "U9") (pin "12") (pinfunction "SDA/CDIN(M1)_12") (pintype "passive"))
    )
    (net (code "67") (name "Net-(U9-XTI)") (class "Default")
      (node (ref "R157") (pin "2") (pinfunction "2_2") (pintype "passive"))
      (node (ref "U9") (pin "2") (pinfunction "XTI_2") (pintype "passive"))
    )
    (net (code "68") (name "Net-(U10A-1IN+)") (class "Default")
      (node (ref "C135") (pin "2") (pinfunction "2_2") (pintype "passive"))
      (node (ref "C138") (pin "1") (pinfunction "1_1") (pintype "passive"))
      (node (ref "R152") (pin "1") (pinfunction "1_1") (pintype "passive"))
      (node (ref "U10") (pin "3") (pinfunction "1IN+_3") (pintype "passive"))
    )
    (net (code "69") (name "Net-(U10A-1IN-)") (class "Default")
      (node (ref "C133") (pin "1") (pinfunction "1_1") (pintype "passive"))
      (node (ref "C135") (pin "1") (pinfunction "1_1") (pintype "passive"))
      (node (ref "R144") (pin "1") (pinfunction "1_1") (pintype "passive"))
      (node (ref "R148") (pin "2") (pinfunction "2_2") (pintype "passive"))
      (node (ref "U10") (pin "2") (pinfunction "1IN-_2") (pintype "passive"))
    )
    (net (code "70") (name "Net-(U10A-1OUT)") (class "Default")
      (node (ref "C133") (pin "2") (pinfunction "2_2") (pintype "passive"))
      (node (ref "R144") (pin "2") (pinfunction "2_2") (pintype "passive"))
      (node (ref "R150") (pin "1") (pinfunction "1_1") (pintype "passive"))
      (node (ref "R154") (pin "2") (pinfunction "2_2") (pintype "passive"))
      (node (ref "U10") (pin "1") (pinfunction "1OUT_1") (pintype "passive"))
    )
    (net (code "71") (name "Net-(U10B-2IN+)") (class "Default")
      (node (ref "C140") (pin "1") (pinfunction "1_1") (pintype "passive"))
      (node (ref "R156") (pin "1") (pinfunction "1_1") (pintype "passive"))
      (node (ref "U10") (pin "5") (pinfunction "2IN+_5") (pintype "passive"))
    )
    (net (code "72") (name "Net-(U10B-2IN-)") (class "Default")
      (node (ref "C139") (pin "1") (pinfunction "1_1") (pintype "passive"))
      (node (ref "R153") (pin "1") (pinfunction "1_1") (pintype "passive"))
      (node (ref "R154") (pin "1") (pinfunction "1_1") (pintype "passive"))
      (node (ref "U10") (pin "6") (pinfunction "2IN-_6") (pintype "passive"))
    )
    (net (code "73") (name "Net-(U10B-2OUT)") (class "Default")
      (node (ref "C139") (pin "2") (pinfunction "2_2") (pintype "passive"))
      (node (ref "R153") (pin "2") (pinfunction "2_2") (pintype "passive"))
      (node (ref "R155") (pin "1") (pinfunction "1_1") (pintype "passive"))
      (node (ref "U10") (pin "7") (pinfunction "2OUT_7") (pintype "passive"))
    )
    (net (code "74") (name "Net-(U11A-1IN+)") (class "Default")
      (node (ref "C144") (pin "2") (pinfunction "2_2") (pintype "passive"))
      (node (ref "C148") (pin "1") (pinfunction "1_1") (pintype "passive"))
      (node (ref "R168") (pin "2") (pinfunction "2_2") (pintype "passive"))
      (node (ref "U11") (pin "3") (pinfunction "1IN+_3") (pintype "passive"))
    )
    (net (code "75") (name "Net-(U11A-1IN-)") (class "Default")
      (node (ref "C142") (pin "1") (pinfunction "1_1") (pintype "passive"))
      (node (ref "C144") (pin "1") (pinfunction "1_1") (pintype "passive"))
      (node (ref "R162") (pin "2") (pinfunction "2_2") (pintype "passive"))
      (node (ref "U11") (pin "2") (pinfunction "1IN-_2") (pintype "passive"))
    )
    (net (code "76") (name "Net-(U11B-2IN+)") (class "Default")
      (node (ref "C152") (pin "2") (pinfunction "2_2") (pintype "passive"))
      (node (ref "C154") (pin "1") (pinfunction "1_1") (pintype "passive"))
      (node (ref "R183") (pin "2") (pinfunction "2_2") (pintype "passive"))
      (node (ref "U11") (pin "5") (pinfunction "2IN+_5") (pintype "passive"))
    )
    (net (code "77") (name "Net-(U11B-2IN-)") (class "Default")
      (node (ref "C149") (pin "1") (pinfunction "1_1") (pintype "passive"))
      (node (ref "C152") (pin "1") (pinfunction "1_1") (pintype "passive"))
      (node (ref "R180") (pin "2") (pinfunction "2_2") (pintype "passive"))
      (node (ref "U11") (pin "6") (pinfunction "2IN-_6") (pintype "passive"))
    )
    (net (code "78") (name "Net-(ZD1-A)") (class "Default")
      (node (ref "R173") (pin "2") (pinfunction "2_2") (pintype "passive"))
      (node (ref "ZD1") (pin "1") (pinfunction "A_1") (pintype "passive"))
    )
    (net (code "79") (name "unconnected-(U9-XT0-Pad1)") (class "Default")
      (node (ref "U9") (pin "1") (pinfunction "XT0_1") (pintype "passive+no_connect"))
    )
    (net (code "80") (name "unconnected-(U9-~{AMUTEC}-Pad23)") (class "Default")
      (node (ref "U9") (pin "23") (pinfunction "~{AMUTEC}_23") (pintype "passive+no_connect"))
    )
    (net (code "81") (name "unconnected-(U9-~{BMUTEC}-Pad28)") (class "Default")
      (node (ref "U9") (pin "28") (pinfunction "~{BMUTEC}_28") (pintype "passive+no_connect"))
    )
  )
)
